# NS_Integrator.net
KiCad netlist of a schematic drawn in EAGLE
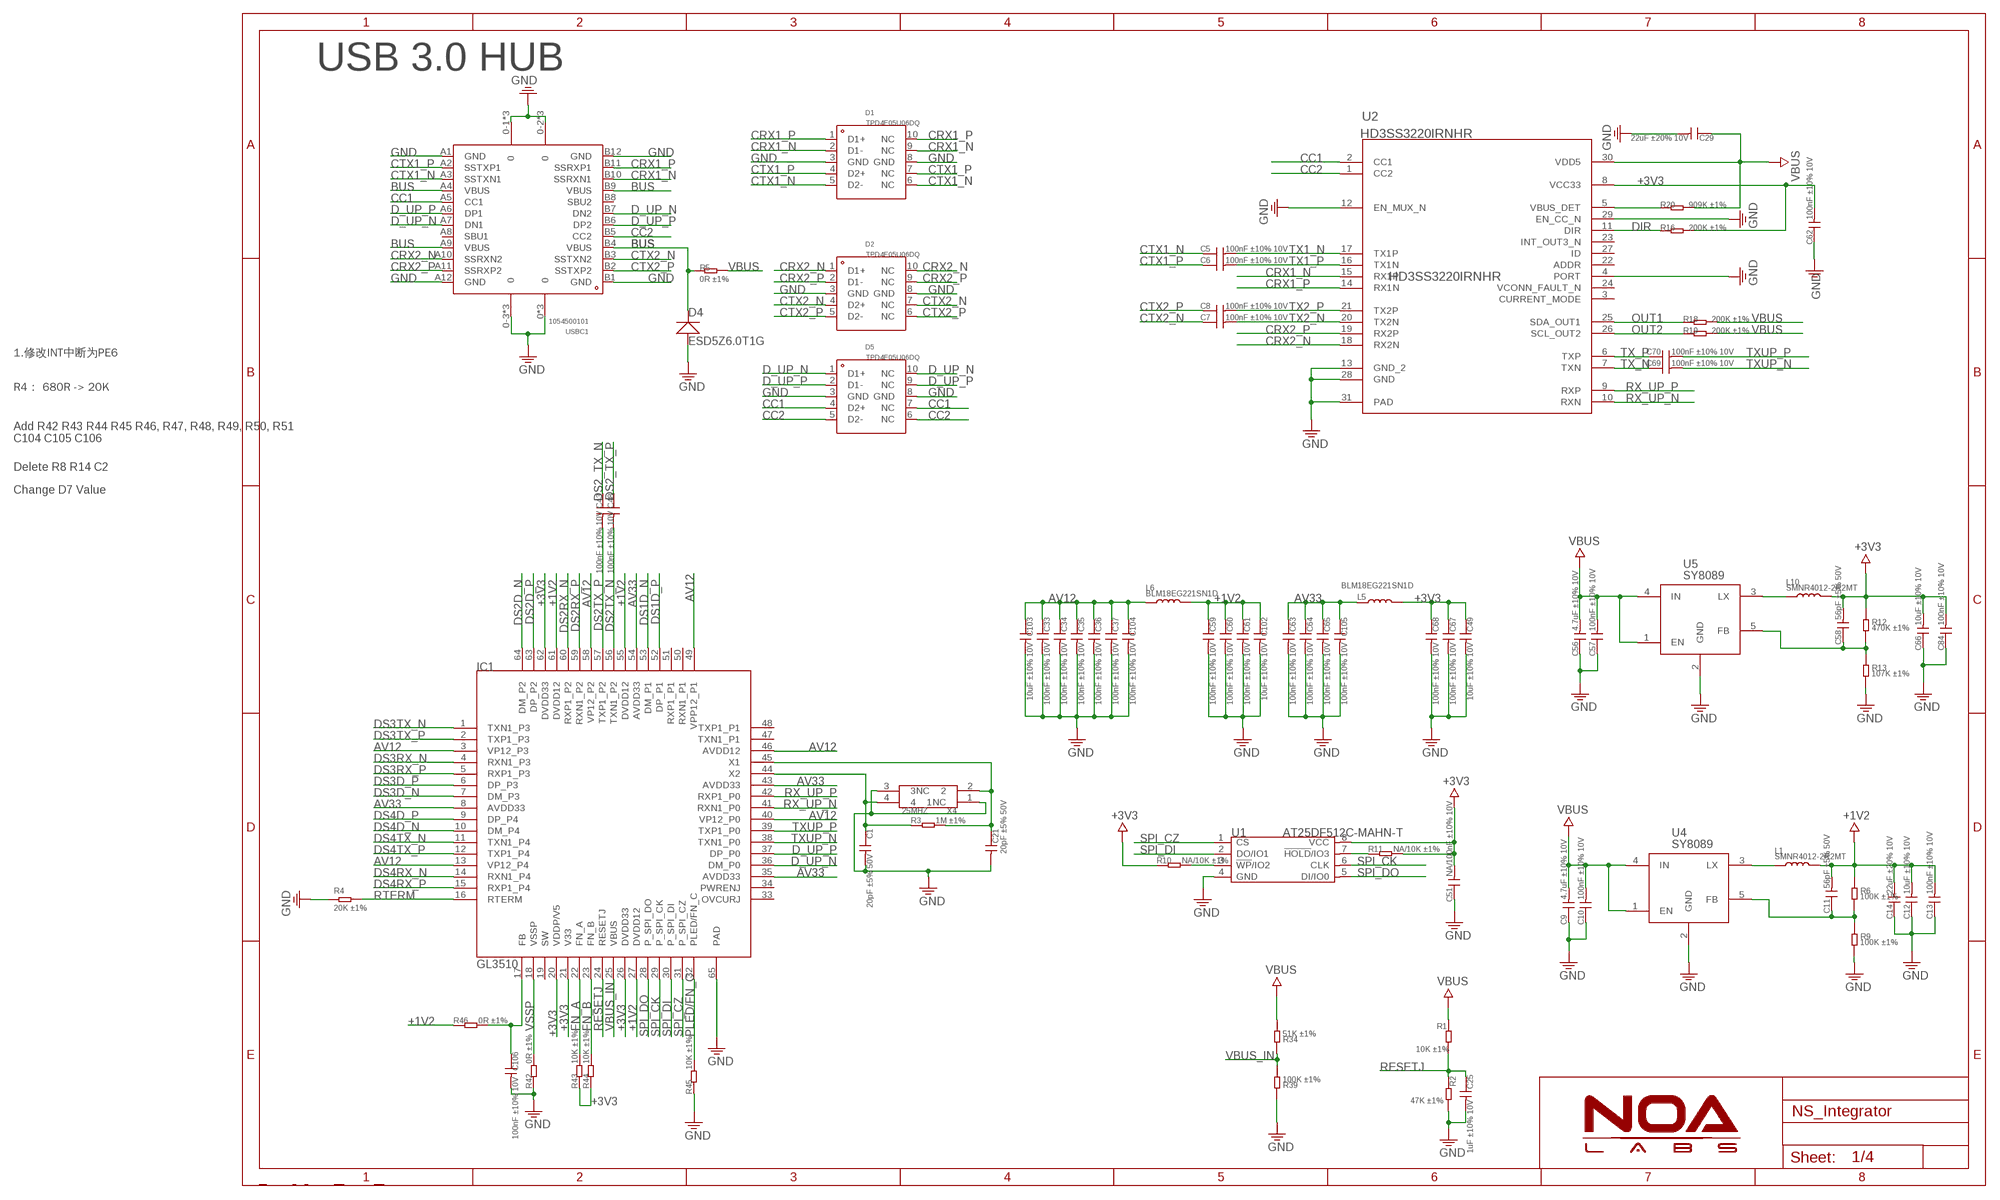
[diagram p0: schematic, sheet 1]
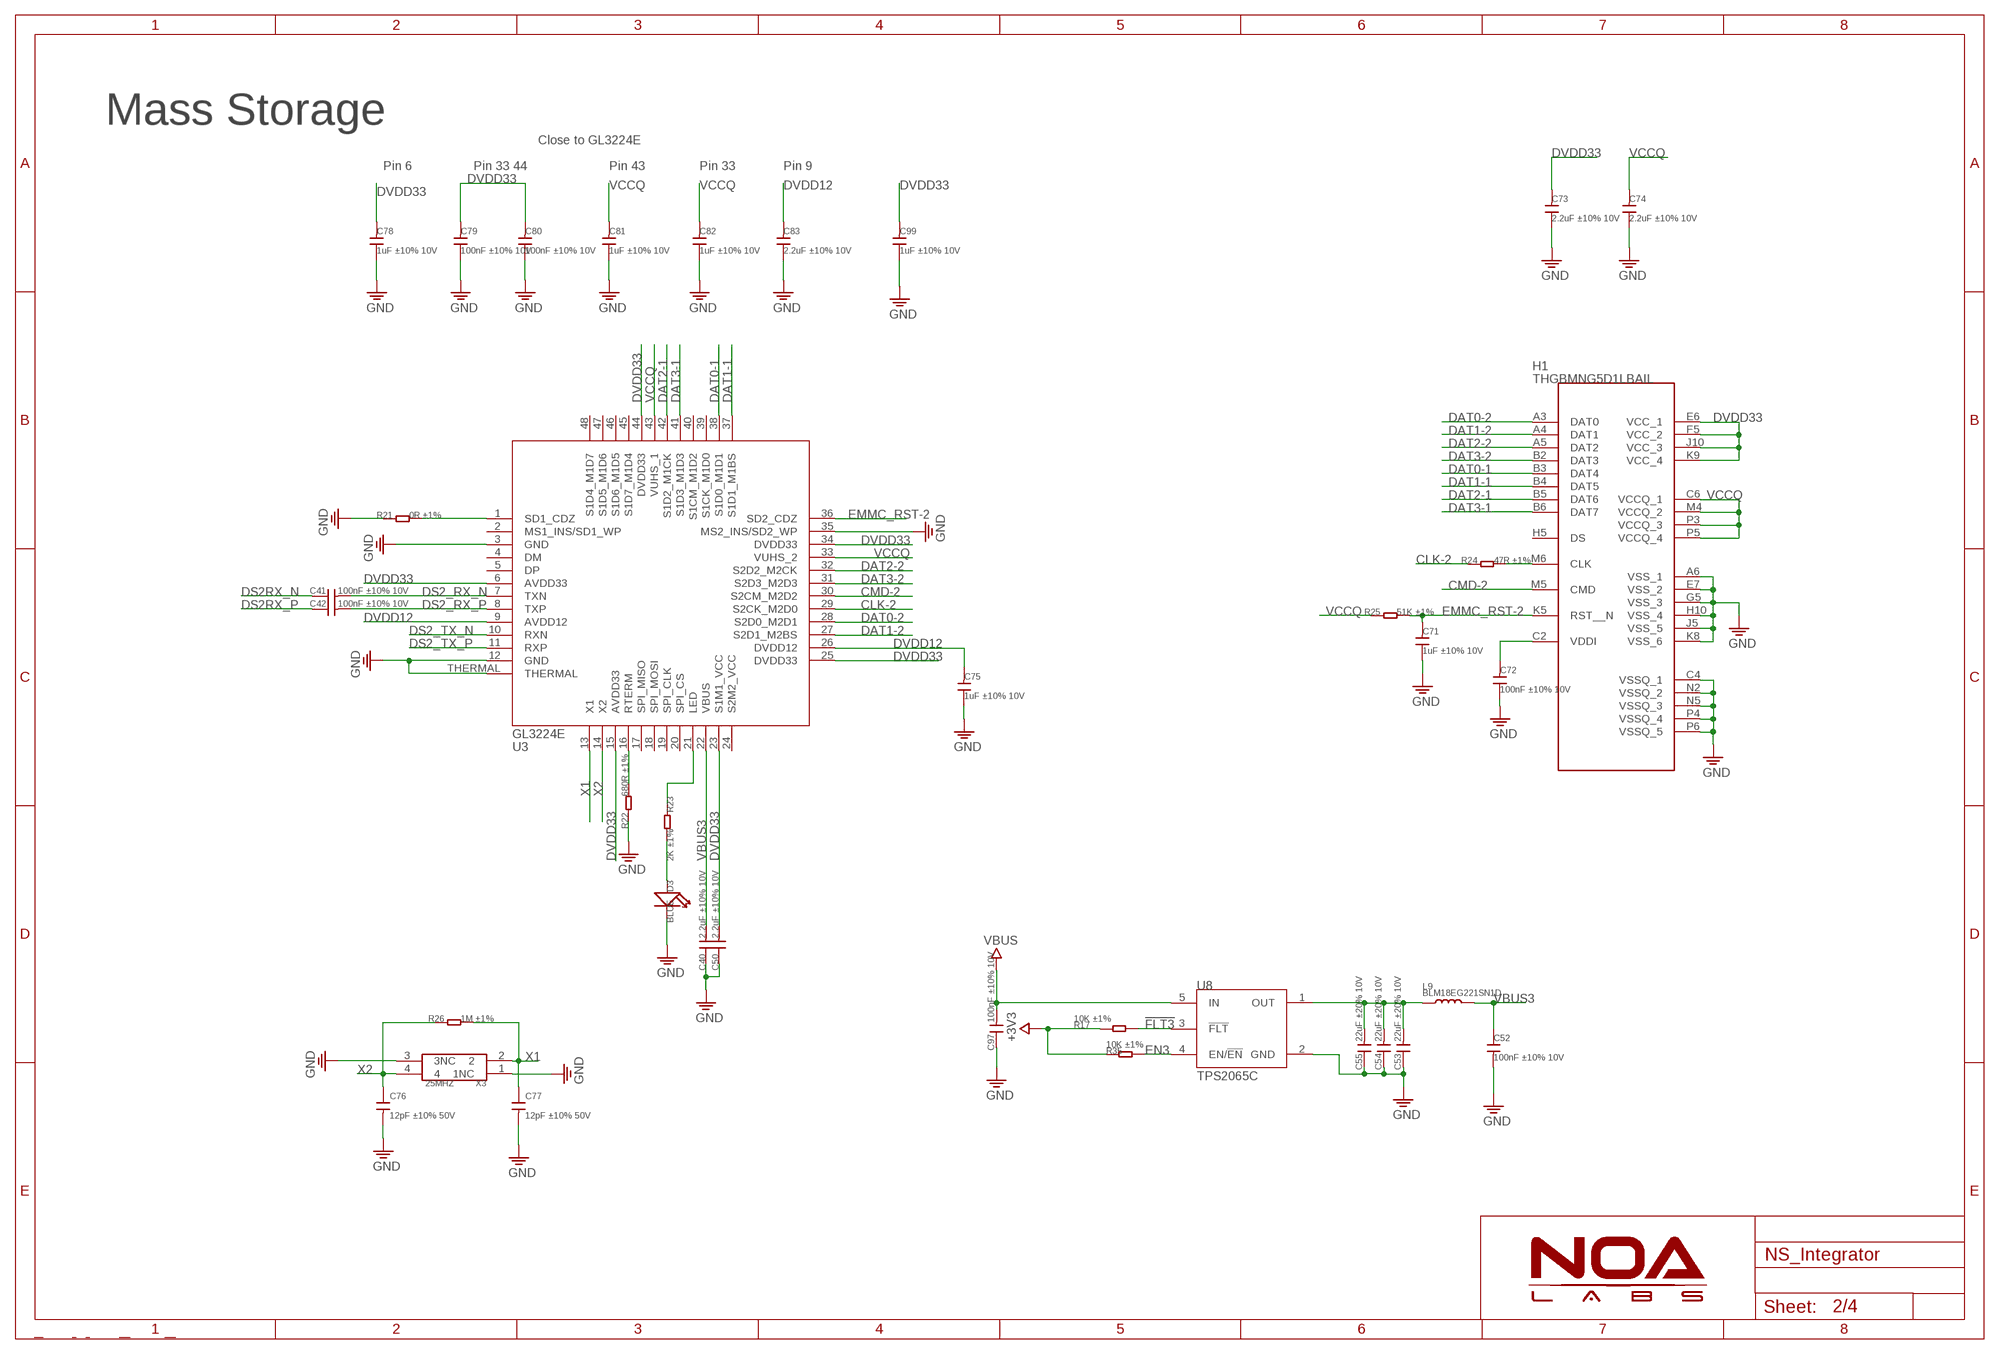
[diagram p1: schematic, sheet 2]
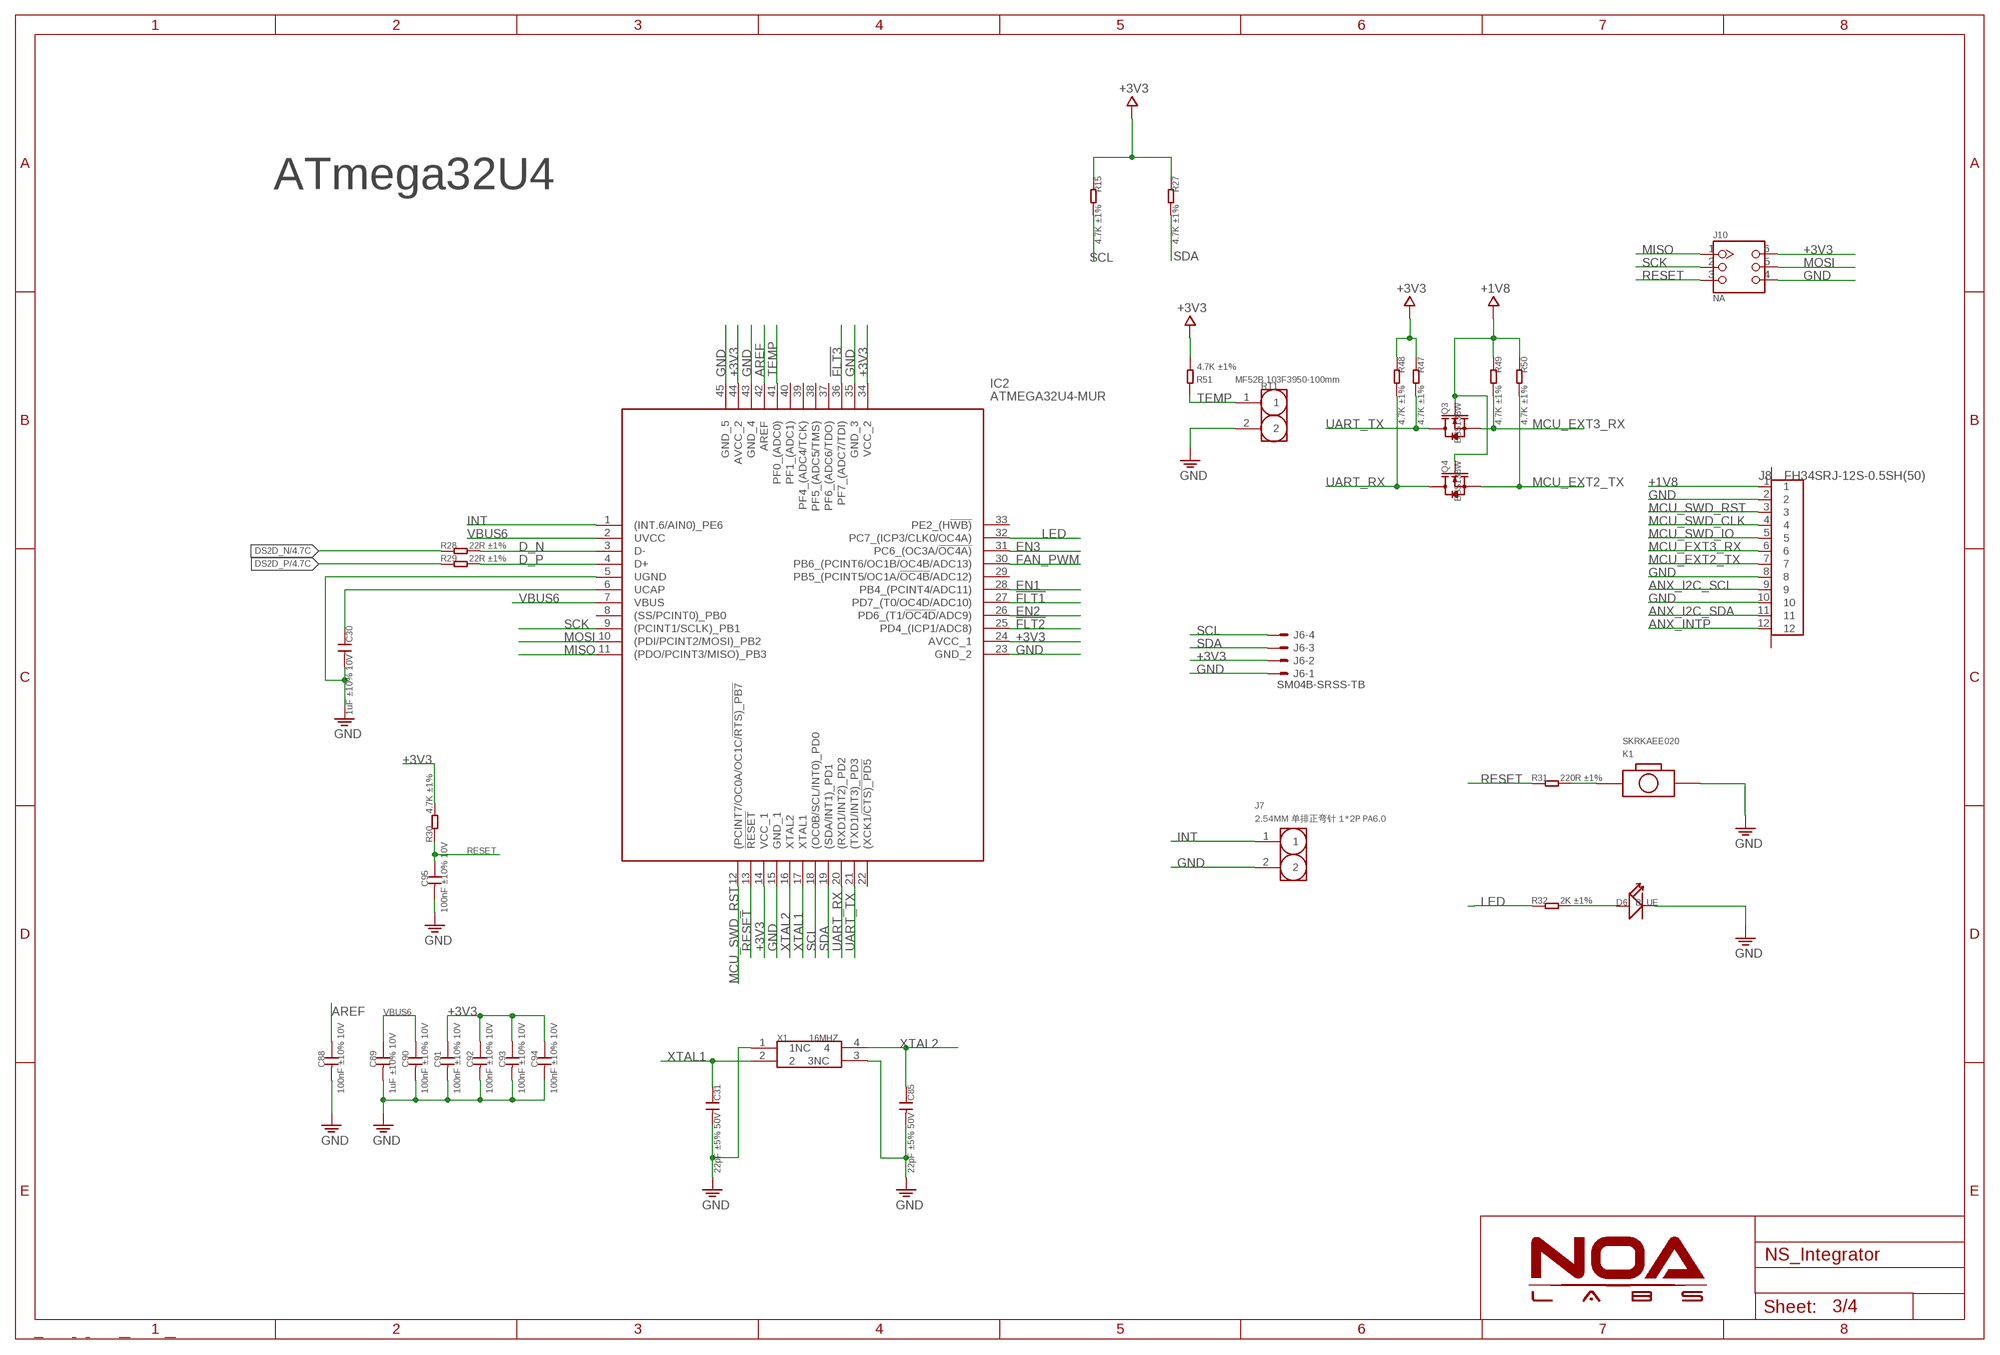
[diagram p2: schematic, sheet 3]
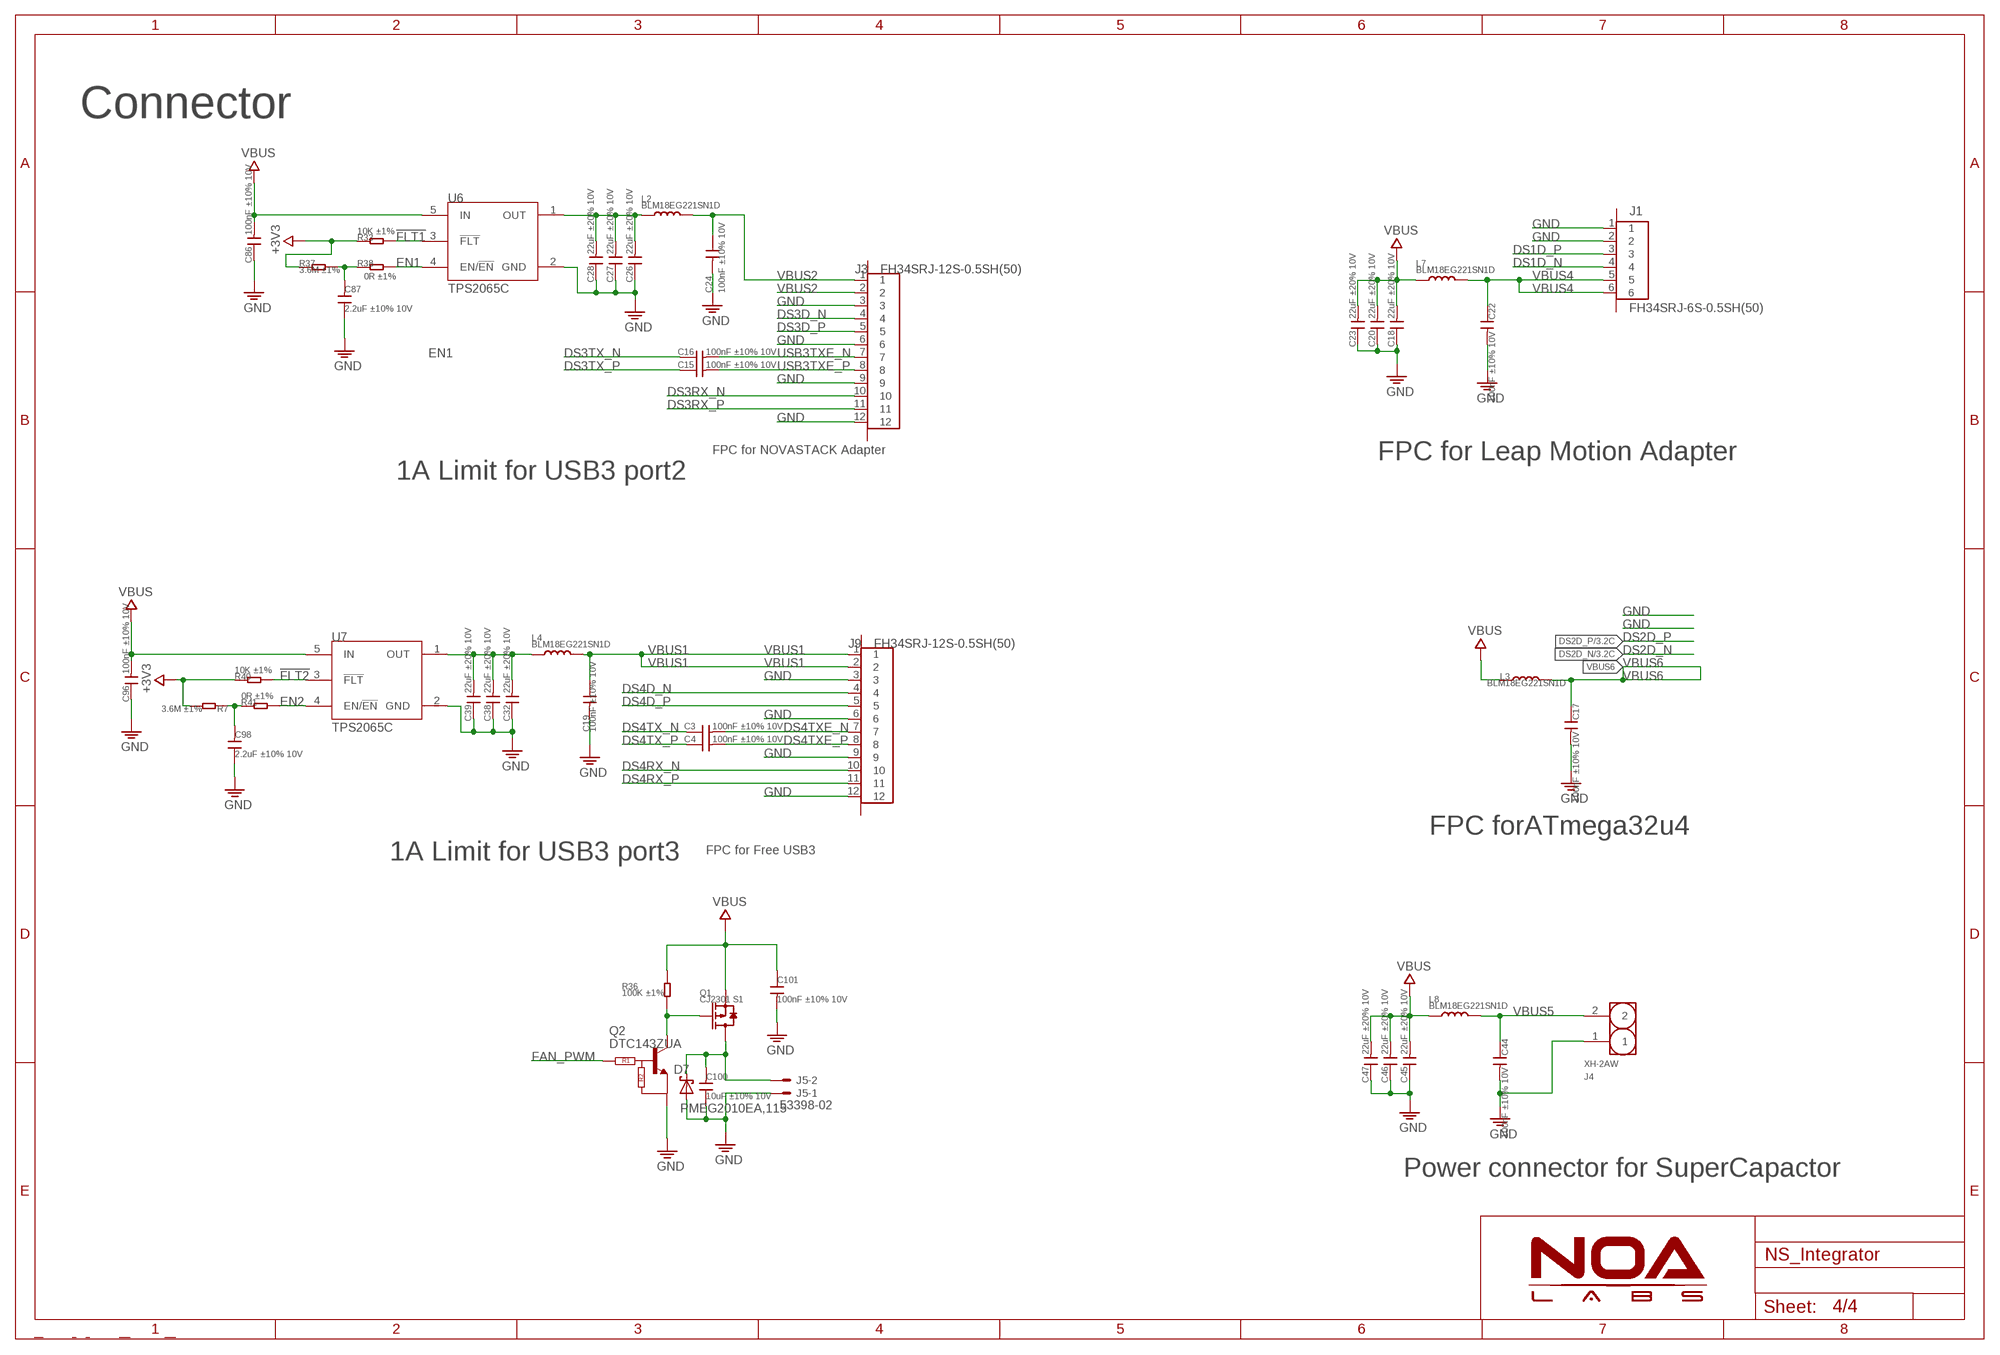
[diagram p3: schematic, sheet 4]

(export (version "E")
  (design (tool "Eeschema 10.0.6"))
  (components
    (comp (ref "C40")
      (value "2.2uF ±10% 10V")
      (footprint "eagle-import:C0402")
      (libsource (lib "eagle-import") (part "C-0402"))
    )
    (comp (ref "C41")
      (value "100nF ±10% 10V")
      (footprint "eagle-import:C0201")
      (libsource (lib "eagle-import") (part "C-0201"))
    )
    (comp (ref "C42")
      (value "100nF ±10% 10V")
      (footprint "eagle-import:C0201")
      (libsource (lib "eagle-import") (part "C-0201"))
    )
    (comp (ref "C50")
      (value "2.2uF ±10% 10V")
      (footprint "eagle-import:C0402")
      (libsource (lib "eagle-import") (part "C-0402"))
    )
    (comp (ref "C52")
      (value "100nF ±10% 10V")
      (footprint "eagle-import:C0402")
      (libsource (lib "eagle-import") (part "C-0402"))
    )
    (comp (ref "C53")
      (value "22uF ±20% 10V")
      (footprint "eagle-import:C0603")
      (libsource (lib "eagle-import") (part "C-0603"))
    )
    (comp (ref "C54")
      (value "22uF ±20% 10V")
      (footprint "eagle-import:C0603")
      (libsource (lib "eagle-import") (part "C-0603"))
    )
    (comp (ref "C55")
      (value "22uF ±20% 10V")
      (footprint "eagle-import:C0603")
      (libsource (lib "eagle-import") (part "C-0603"))
    )
    (comp (ref "C71")
      (value "1uF ±10% 10V")
      (footprint "eagle-import:C0402")
      (libsource (lib "eagle-import") (part "C-0402"))
    )
    (comp (ref "C72")
      (value "100nF ±10% 10V")
      (footprint "eagle-import:C0402")
      (libsource (lib "eagle-import") (part "C-0402"))
    )
    (comp (ref "C73")
      (value "2.2uF ±10% 10V")
      (footprint "eagle-import:C0402")
      (libsource (lib "eagle-import") (part "C-0402"))
    )
    (comp (ref "C74")
      (value "2.2uF ±10% 10V")
      (footprint "eagle-import:C0402")
      (libsource (lib "eagle-import") (part "C-0402"))
    )
    (comp (ref "C75")
      (value "1uF ±10% 10V")
      (footprint "eagle-import:C0402")
      (libsource (lib "eagle-import") (part "C-0402"))
    )
    (comp (ref "C76")
      (value "12pF ±10% 50V")
      (footprint "eagle-import:C0402")
      (libsource (lib "eagle-import") (part "C-0402"))
    )
    (comp (ref "C77")
      (value "12pF ±10% 50V")
      (footprint "eagle-import:C0402")
      (libsource (lib "eagle-import") (part "C-0402"))
    )
    (comp (ref "C78")
      (value "1uF ±10% 10V")
      (footprint "eagle-import:C0402")
      (libsource (lib "eagle-import") (part "C-0402"))
    )
    (comp (ref "C79")
      (value "100nF ±10% 10V")
      (footprint "eagle-import:C0402")
      (libsource (lib "eagle-import") (part "C-0402"))
    )
    (comp (ref "C80")
      (value "100nF ±10% 10V")
      (footprint "eagle-import:C0402")
      (libsource (lib "eagle-import") (part "C-0402"))
    )
    (comp (ref "C81")
      (value "1uF ±10% 10V")
      (footprint "eagle-import:C0402")
      (libsource (lib "eagle-import") (part "C-0402"))
    )
    (comp (ref "C82")
      (value "1uF ±10% 10V")
      (footprint "eagle-import:C0402")
      (libsource (lib "eagle-import") (part "C-0402"))
    )
    (comp (ref "C83")
      (value "2.2uF ±10% 10V")
      (footprint "eagle-import:C0402")
      (libsource (lib "eagle-import") (part "C-0402"))
    )
    (comp (ref "C97")
      (value "100nF ±10% 10V")
      (footprint "eagle-import:C0402")
      (libsource (lib "eagle-import") (part "C-0402"))
    )
    (comp (ref "C99")
      (value "1uF ±10% 10V")
      (footprint "eagle-import:C0402")
      (libsource (lib "eagle-import") (part "C-0402"))
    )
    (comp (ref "D3")
      (value "BLUE")
      (footprint "eagle-import:0402_LED")
      (libsource (lib "eagle-import") (part "LED-0402LED"))
    )
    (comp (ref "H1")
      (value "THGBMNG5D1LBAIL")
      (footprint "eagle-import:BGA153C50P14X14_11.5X13")
      (fields
        (field (name "MANUFACTURER_PART_NUMBER") "IS21ES04G-JCLI-TR")
        (field (name "MOUSER_PART_NUMBER") "870-IS21ES04GJCLITR")
      )
      (libsource (lib "eagle-import") (part "EMMC-SPECIALPAD"))
    )
    (comp (ref "L9")
      (value "BLM18EG221SN1D")
      (footprint "eagle-import:L0603")
      (libsource (lib "eagle-import") (part "L-0603"))
    )
    (comp (ref "R17")
      (value "10K ±1%")
      (footprint "eagle-import:R0402")
      (libsource (lib "eagle-import") (part "R-0402"))
    )
    (comp (ref "R21")
      (value "0R ±1%")
      (footprint "eagle-import:R0402")
      (libsource (lib "eagle-import") (part "R-0402"))
    )
    (comp (ref "R22")
      (value "680R ±1%")
      (footprint "eagle-import:R0402")
      (libsource (lib "eagle-import") (part "R-0402"))
    )
    (comp (ref "R23")
      (value "2K ±1%")
      (footprint "eagle-import:R0402")
      (libsource (lib "eagle-import") (part "R-0402"))
    )
    (comp (ref "R24")
      (value "47R ±1%")
      (footprint "eagle-import:R0402")
      (libsource (lib "eagle-import") (part "R-0402"))
    )
    (comp (ref "R25")
      (value "51K ±1%")
      (footprint "eagle-import:R0402")
      (libsource (lib "eagle-import") (part "R-0402"))
    )
    (comp (ref "R26")
      (value "1M ±1%")
      (footprint "eagle-import:R0402")
      (libsource (lib "eagle-import") (part "R-0402"))
    )
    (comp (ref "R35")
      (value "10K ±1%")
      (footprint "eagle-import:R0402")
      (libsource (lib "eagle-import") (part "R-0402"))
    )
    (comp (ref "U3")
      (value "GL3224E")
      (footprint "eagle-import:TQFN48_7MM")
      (libsource (lib "eagle-import") (part "GL3224E"))
    )
    (comp (ref "U8")
      (value "TPS2065C")
      (footprint "eagle-import:SOT23-5")
      (libsource (lib "eagle-import") (part "TPS20XXC"))
    )
    (comp (ref "X3")
      (value "25MHZ")
      (footprint "eagle-import:4P-SMD-2X1.6MM")
      (libsource (lib "eagle-import") (part "CRYSTAL-XTAL-4P"))
    )
    (comp (ref "C1")
      (value "20pF ±5% 50V")
      (footprint "eagle-import:C0402")
      (libsource (lib "eagle-import") (part "C-0402"))
    )
    (comp (ref "C5")
      (value "100nF ±10% 10V")
      (footprint "eagle-import:C0201")
      (libsource (lib "eagle-import") (part "C-0201"))
    )
    (comp (ref "C6")
      (value "100nF ±10% 10V")
      (footprint "eagle-import:C0201")
      (libsource (lib "eagle-import") (part "C-0201"))
    )
    (comp (ref "C7")
      (value "100nF ±10% 10V")
      (footprint "eagle-import:C0201")
      (libsource (lib "eagle-import") (part "C-0201"))
    )
    (comp (ref "C8")
      (value "100nF ±10% 10V")
      (footprint "eagle-import:C0201")
      (libsource (lib "eagle-import") (part "C-0201"))
    )
    (comp (ref "C9")
      (value "4.7uF ±10% 10V")
      (footprint "eagle-import:C0603")
      (libsource (lib "eagle-import") (part "C-0603"))
    )
    (comp (ref "C10")
      (value "100nF ±10% 10V")
      (footprint "eagle-import:C0402")
      (libsource (lib "eagle-import") (part "C-0402"))
    )
    (comp (ref "C11")
      (value "56pF ±5% 50V")
      (footprint "eagle-import:C0402")
      (libsource (lib "eagle-import") (part "C-0402"))
    )
    (comp (ref "C12")
      (value "10uF ±10% 10V")
      (footprint "eagle-import:C0603")
      (libsource (lib "eagle-import") (part "C-0603"))
    )
    (comp (ref "C13")
      (value "100nF ±10% 10V")
      (footprint "eagle-import:C0402")
      (libsource (lib "eagle-import") (part "C-0402"))
    )
    (comp (ref "C14")
      (value "22uF ±20% 10V")
      (footprint "eagle-import:C0805")
      (libsource (lib "eagle-import") (part "C-0805"))
    )
    (comp (ref "C21")
      (value "20pF ±5% 50V")
      (footprint "eagle-import:C0402")
      (libsource (lib "eagle-import") (part "C-0402"))
    )
    (comp (ref "C25")
      (value "1uF ±10% 10V")
      (footprint "eagle-import:C0402")
      (libsource (lib "eagle-import") (part "C-0402"))
    )
    (comp (ref "C29")
      (value "22uF ±20% 10V")
      (footprint "eagle-import:C0805")
      (libsource (lib "eagle-import") (part "C-0805"))
    )
    (comp (ref "C33")
      (value "100nF ±10% 10V")
      (footprint "eagle-import:C0402")
      (libsource (lib "eagle-import") (part "C-0402"))
    )
    (comp (ref "C34")
      (value "100nF ±10% 10V")
      (footprint "eagle-import:C0402")
      (libsource (lib "eagle-import") (part "C-0402"))
    )
    (comp (ref "C35")
      (value "100nF ±10% 10V")
      (footprint "eagle-import:C0402")
      (libsource (lib "eagle-import") (part "C-0402"))
    )
    (comp (ref "C36")
      (value "100nF ±10% 10V")
      (footprint "eagle-import:C0402")
      (libsource (lib "eagle-import") (part "C-0402"))
    )
    (comp (ref "C37")
      (value "100nF ±10% 10V")
      (footprint "eagle-import:C0402")
      (libsource (lib "eagle-import") (part "C-0402"))
    )
    (comp (ref "C43")
      (value "100nF ±10% 10V")
      (footprint "eagle-import:C0201")
      (libsource (lib "eagle-import") (part "C-0201"))
    )
    (comp (ref "C48")
      (value "100nF ±10% 10V")
      (footprint "eagle-import:C0201")
      (libsource (lib "eagle-import") (part "C-0201"))
    )
    (comp (ref "C49")
      (value "10uF ±10% 10V")
      (footprint "eagle-import:C0603")
      (libsource (lib "eagle-import") (part "C-0603"))
    )
    (comp (ref "C51")
      (value "NA/100nF ±10% 10V")
      (footprint "eagle-import:C0402")
      (libsource (lib "eagle-import") (part "C-0402"))
    )
    (comp (ref "C56")
      (value "4.7uF ±10% 10V")
      (footprint "eagle-import:C0603")
      (libsource (lib "eagle-import") (part "C-0603"))
    )
    (comp (ref "C57")
      (value "100nF ±10% 10V")
      (footprint "eagle-import:C0402")
      (libsource (lib "eagle-import") (part "C-0402"))
    )
    (comp (ref "C58")
      (value "56pF ±5% 50V")
      (footprint "eagle-import:C0402")
      (libsource (lib "eagle-import") (part "C-0402"))
    )
    (comp (ref "C59")
      (value "100nF ±10% 10V")
      (footprint "eagle-import:C0402")
      (libsource (lib "eagle-import") (part "C-0402"))
    )
    (comp (ref "C60")
      (value "100nF ±10% 10V")
      (footprint "eagle-import:C0402")
      (libsource (lib "eagle-import") (part "C-0402"))
    )
    (comp (ref "C61")
      (value "100nF ±10% 10V")
      (footprint "eagle-import:C0402")
      (libsource (lib "eagle-import") (part "C-0402"))
    )
    (comp (ref "C62")
      (value "100nF ±10% 10V")
      (footprint "eagle-import:C0402")
      (libsource (lib "eagle-import") (part "C-0402"))
    )
    (comp (ref "C63")
      (value "100nF ±10% 10V")
      (footprint "eagle-import:C0402")
      (libsource (lib "eagle-import") (part "C-0402"))
    )
    (comp (ref "C64")
      (value "100nF ±10% 10V")
      (footprint "eagle-import:C0402")
      (libsource (lib "eagle-import") (part "C-0402"))
    )
    (comp (ref "C65")
      (value "100nF ±10% 10V")
      (footprint "eagle-import:C0402")
      (libsource (lib "eagle-import") (part "C-0402"))
    )
    (comp (ref "C66")
      (value "10uF ±10% 10V")
      (footprint "eagle-import:C0603")
      (libsource (lib "eagle-import") (part "C-0603"))
    )
    (comp (ref "C67")
      (value "100nF ±10% 10V")
      (footprint "eagle-import:C0402")
      (libsource (lib "eagle-import") (part "C-0402"))
    )
    (comp (ref "C68")
      (value "100nF ±10% 10V")
      (footprint "eagle-import:C0402")
      (libsource (lib "eagle-import") (part "C-0402"))
    )
    (comp (ref "C69")
      (value "100nF ±10% 10V")
      (footprint "eagle-import:C0201")
      (libsource (lib "eagle-import") (part "C-0201"))
    )
    (comp (ref "C70")
      (value "100nF ±10% 10V")
      (footprint "eagle-import:C0201")
      (libsource (lib "eagle-import") (part "C-0201"))
    )
    (comp (ref "C84")
      (value "100nF ±10% 10V")
      (footprint "eagle-import:C0402")
      (libsource (lib "eagle-import") (part "C-0402"))
    )
    (comp (ref "C102")
      (value "10uF ±10% 10V")
      (footprint "eagle-import:C0603")
      (libsource (lib "eagle-import") (part "C-0603"))
    )
    (comp (ref "C103")
      (value "10uF ±10% 10V")
      (footprint "eagle-import:C0603")
      (libsource (lib "eagle-import") (part "C-0603"))
    )
    (comp (ref "C104")
      (value "100nF ±10% 10V")
      (footprint "eagle-import:C0402")
      (libsource (lib "eagle-import") (part "C-0402"))
    )
    (comp (ref "C105")
      (value "100nF ±10% 10V")
      (footprint "eagle-import:C0402")
      (libsource (lib "eagle-import") (part "C-0402"))
    )
    (comp (ref "C106")
      (value "100nF ±10% 10V")
      (footprint "eagle-import:C0402")
      (libsource (lib "eagle-import") (part "C-0402"))
    )
    (comp (ref "D1")
      (value "TPD4E05U06DQ")
      (footprint "eagle-import:USON-10_L2.5-W1.0-P0.50-BL")
      (fields
        (field (name "BOM_MANUFACTURER_PART") "TPD4E05U06DQAR")
        (field (name "BOM_SUPPLIER_PART") "C138714")
        (field (name "CONTRIBUTOR") "LCSC")
      )
      (libsource (lib "eagle-import") (part "TPD4E05U06DQARTPD4E05U06DQAR_C138714_USON-10_L2.5-W1.0-P0.50-BL"))
    )
    (comp (ref "D2")
      (value "TPD4E05U06DQ")
      (footprint "eagle-import:USON-10_L2.5-W1.0-P0.50-BL")
      (fields
        (field (name "BOM_MANUFACTURER_PART") "TPD4E05U06DQAR")
        (field (name "BOM_SUPPLIER_PART") "C138714")
        (field (name "CONTRIBUTOR") "LCSC")
      )
      (libsource (lib "eagle-import") (part "TPD4E05U06DQARTPD4E05U06DQAR_C138714_USON-10_L2.5-W1.0-P0.50-BL"))
    )
    (comp (ref "D4")
      (value "ESD5Z6.0T1G")
      (footprint "eagle-import:SOD523")
      (libsource (lib "eagle-import") (part "D-0603"))
    )
    (comp (ref "D5")
      (value "TPD4E05U06DQ")
      (footprint "eagle-import:USON-10_L2.5-W1.0-P0.50-BL")
      (fields
        (field (name "BOM_MANUFACTURER_PART") "TPD4E05U06DQAR")
        (field (name "BOM_SUPPLIER_PART") "C138714")
        (field (name "CONTRIBUTOR") "LCSC")
      )
      (libsource (lib "eagle-import") (part "TPD4E05U06DQARTPD4E05U06DQAR_C138714_USON-10_L2.5-W1.0-P0.50-BL"))
    )
    (comp (ref "IC1")
      (value "GL3510")
      (footprint "eagle-import:QFN40P800X800X80-65N")
      (libsource (lib "eagle-import") (part "GL3510"))
    )
    (comp (ref "L1")
      (value "SMNR4012-2R2MT")
      (footprint "eagle-import:L4012")
      (libsource (lib "eagle-import") (part "L-4012"))
    )
    (comp (ref "L5")
      (value "BLM18EG221SN1D")
      (footprint "eagle-import:L0603")
      (libsource (lib "eagle-import") (part "L-0603"))
    )
    (comp (ref "L6")
      (value "BLM18EG221SN1D")
      (footprint "eagle-import:L0603")
      (libsource (lib "eagle-import") (part "L-0603"))
    )
    (comp (ref "L10")
      (value "SMNR4012-2R2MT")
      (footprint "eagle-import:L4012")
      (libsource (lib "eagle-import") (part "L-4012"))
    )
    (comp (ref "R1")
      (value "10K ±1%")
      (footprint "eagle-import:R0402")
      (libsource (lib "eagle-import") (part "R-0402"))
    )
    (comp (ref "R2")
      (value "47K ±1%")
      (footprint "eagle-import:R0402")
      (libsource (lib "eagle-import") (part "R-0402"))
    )
    (comp (ref "R3")
      (value "1M ±1%")
      (footprint "eagle-import:R0402")
      (libsource (lib "eagle-import") (part "R-0402"))
    )
    (comp (ref "R4")
      (value "20K ±1%")
      (footprint "eagle-import:R0402")
      (libsource (lib "eagle-import") (part "R-0402"))
    )
    (comp (ref "R5")
      (value "0R ±1%")
      (footprint "eagle-import:R0805")
      (libsource (lib "eagle-import") (part "R-0805"))
    )
    (comp (ref "R6")
      (value "100K ±1%")
      (footprint "eagle-import:R0402")
      (libsource (lib "eagle-import") (part "R-0402"))
    )
    (comp (ref "R9")
      (value "100K ±1%")
      (footprint "eagle-import:R0402")
      (libsource (lib "eagle-import") (part "R-0402"))
    )
    (comp (ref "R10")
      (value "NA/10K ±1%")
      (footprint "eagle-import:R0402")
      (libsource (lib "eagle-import") (part "R-0402"))
    )
    (comp (ref "R11")
      (value "NA/10K ±1%")
      (footprint "eagle-import:R0402")
      (libsource (lib "eagle-import") (part "R-0402"))
    )
    (comp (ref "R12")
      (value "470K ±1%")
      (footprint "eagle-import:R0402")
      (libsource (lib "eagle-import") (part "R-0402"))
    )
    (comp (ref "R13")
      (value "107K ±1%")
      (footprint "eagle-import:R0402")
      (libsource (lib "eagle-import") (part "R-0402"))
    )
    (comp (ref "R16")
      (value "200K ±1%")
      (footprint "eagle-import:R0402")
      (libsource (lib "eagle-import") (part "R-0402"))
    )
    (comp (ref "R18")
      (value "200K ±1%")
      (footprint "eagle-import:R0402")
      (libsource (lib "eagle-import") (part "R-0402"))
    )
    (comp (ref "R19")
      (value "200K ±1%")
      (footprint "eagle-import:R0402")
      (libsource (lib "eagle-import") (part "R-0402"))
    )
    (comp (ref "R20")
      (value "909K ±1%")
      (footprint "eagle-import:R0402")
      (libsource (lib "eagle-import") (part "R-0402"))
    )
    (comp (ref "R34")
      (value "51K ±1%")
      (footprint "eagle-import:R0402")
      (libsource (lib "eagle-import") (part "R-0402"))
    )
    (comp (ref "R39")
      (value "100K ±1%")
      (footprint "eagle-import:R0402")
      (libsource (lib "eagle-import") (part "R-0402"))
    )
    (comp (ref "R42")
      (value "0R ±1%")
      (footprint "eagle-import:R0402")
      (libsource (lib "eagle-import") (part "R-0402"))
    )
    (comp (ref "R43")
      (value "10K ±1%")
      (footprint "eagle-import:R0402")
      (libsource (lib "eagle-import") (part "R-0402"))
    )
    (comp (ref "R44")
      (value "10K ±1%")
      (footprint "eagle-import:R0402")
      (libsource (lib "eagle-import") (part "R-0402"))
    )
    (comp (ref "R45")
      (value "10K ±1%")
      (footprint "eagle-import:R0402")
      (libsource (lib "eagle-import") (part "R-0402"))
    )
    (comp (ref "R46")
      (value "0R ±1%")
      (footprint "eagle-import:R0402")
      (libsource (lib "eagle-import") (part "R-0402"))
    )
    (comp (ref "U1")
      (value "AT25DF512C-MAHN-T")
      (footprint "eagle-import:SOIC8-6.0")
      (libsource (lib "eagle-import") (part "W25Q"))
    )
    (comp (ref "U2")
      (value "HD3SS3220IRNHR")
      (footprint "eagle-import:RNH0030A")
      (fields (field (name "MANUFACTURER") "Texas Instruments"))
      (libsource (lib "eagle-import") (part "HD3SS3220IRNHR"))
    )
    (comp (ref "U4")
      (value "SY8089")
      (footprint "eagle-import:SOT23-5")
      (libsource (lib "eagle-import") (part "SY8089"))
    )
    (comp (ref "U5")
      (value "SY8089")
      (footprint "eagle-import:SOT23-5")
      (libsource (lib "eagle-import") (part "SY8089"))
    )
    (comp (ref "USBC1")
      (value "1054500101")
      (footprint "eagle-import:USB-C-SMD_TYPE-C-USB-18")
      (fields
        (field (name "BOM_MANUFACTURER_PART") "105450-0101")
        (field (name "BOM_SUPPLIER_PART") "C134092")
        (field (name "CONTRIBUTOR") "LCSC")
      )
      (libsource (lib "eagle-import") (part "TYPEC-105450-0101105450-0101_USB-C-SMD_TYPE-C-USB-18"))
    )
    (comp (ref "X4")
      (value "25MHZ")
      (footprint "eagle-import:4P-SMD-2X1.6MM")
      (libsource (lib "eagle-import") (part "CRYSTAL-XTAL-4P"))
    )
    (comp (ref "C3")
      (value "100nF ±10% 10V")
      (footprint "eagle-import:C0201")
      (libsource (lib "eagle-import") (part "C-0201"))
    )
    (comp (ref "C4")
      (value "100nF ±10% 10V")
      (footprint "eagle-import:C0201")
      (libsource (lib "eagle-import") (part "C-0201"))
    )
    (comp (ref "C15")
      (value "100nF ±10% 10V")
      (footprint "eagle-import:C0201")
      (libsource (lib "eagle-import") (part "C-0201"))
    )
    (comp (ref "C16")
      (value "100nF ±10% 10V")
      (footprint "eagle-import:C0201")
      (libsource (lib "eagle-import") (part "C-0201"))
    )
    (comp (ref "C17")
      (value "100nF ±10% 10V")
      (footprint "eagle-import:C0402")
      (libsource (lib "eagle-import") (part "C-0402"))
    )
    (comp (ref "C18")
      (value "22uF ±20% 10V")
      (footprint "eagle-import:C0603")
      (libsource (lib "eagle-import") (part "C-0603"))
    )
    (comp (ref "C19")
      (value "100nF ±10% 10V")
      (footprint "eagle-import:C0402")
      (libsource (lib "eagle-import") (part "C-0402"))
    )
    (comp (ref "C20")
      (value "22uF ±20% 10V")
      (footprint "eagle-import:C0603")
      (libsource (lib "eagle-import") (part "C-0603"))
    )
    (comp (ref "C22")
      (value "100nF ±10% 10V")
      (footprint "eagle-import:C0402")
      (libsource (lib "eagle-import") (part "C-0402"))
    )
    (comp (ref "C23")
      (value "22uF ±20% 10V")
      (footprint "eagle-import:C0603")
      (libsource (lib "eagle-import") (part "C-0603"))
    )
    (comp (ref "C24")
      (value "100nF ±10% 10V")
      (footprint "eagle-import:C0402")
      (libsource (lib "eagle-import") (part "C-0402"))
    )
    (comp (ref "C26")
      (value "22uF ±20% 10V")
      (footprint "eagle-import:C0603")
      (libsource (lib "eagle-import") (part "C-0603"))
    )
    (comp (ref "C27")
      (value "22uF ±20% 10V")
      (footprint "eagle-import:C0603")
      (libsource (lib "eagle-import") (part "C-0603"))
    )
    (comp (ref "C28")
      (value "22uF ±20% 10V")
      (footprint "eagle-import:C0603")
      (libsource (lib "eagle-import") (part "C-0603"))
    )
    (comp (ref "C32")
      (value "22uF ±20% 10V")
      (footprint "eagle-import:C0603")
      (libsource (lib "eagle-import") (part "C-0603"))
    )
    (comp (ref "C38")
      (value "22uF ±20% 10V")
      (footprint "eagle-import:C0603")
      (libsource (lib "eagle-import") (part "C-0603"))
    )
    (comp (ref "C39")
      (value "22uF ±20% 10V")
      (footprint "eagle-import:C0603")
      (libsource (lib "eagle-import") (part "C-0603"))
    )
    (comp (ref "C44")
      (value "100nF ±10% 10V")
      (footprint "eagle-import:C0402")
      (libsource (lib "eagle-import") (part "C-0402"))
    )
    (comp (ref "C45")
      (value "22uF ±20% 10V")
      (footprint "eagle-import:C0603")
      (libsource (lib "eagle-import") (part "C-0603"))
    )
    (comp (ref "C46")
      (value "22uF ±20% 10V")
      (footprint "eagle-import:C0603")
      (libsource (lib "eagle-import") (part "C-0603"))
    )
    (comp (ref "C47")
      (value "22uF ±20% 10V")
      (footprint "eagle-import:C0603")
      (libsource (lib "eagle-import") (part "C-0603"))
    )
    (comp (ref "C86")
      (value "100nF ±10% 10V")
      (footprint "eagle-import:C0402")
      (libsource (lib "eagle-import") (part "C-0402"))
    )
    (comp (ref "C87")
      (value "2.2uF ±10% 10V")
      (footprint "eagle-import:C0402")
      (libsource (lib "eagle-import") (part "C-0402"))
    )
    (comp (ref "C96")
      (value "100nF ±10% 10V")
      (footprint "eagle-import:C0402")
      (libsource (lib "eagle-import") (part "C-0402"))
    )
    (comp (ref "C98")
      (value "2.2uF ±10% 10V")
      (footprint "eagle-import:C0402")
      (libsource (lib "eagle-import") (part "C-0402"))
    )
    (comp (ref "C100")
      (value "10uF ±10% 10V")
      (footprint "eagle-import:C0603")
      (libsource (lib "eagle-import") (part "C-0603"))
    )
    (comp (ref "C101")
      (value "100nF ±10% 10V")
      (footprint "eagle-import:C0402")
      (libsource (lib "eagle-import") (part "C-0402"))
    )
    (comp (ref "D7")
      (value "PMEG2010EA,115")
      (footprint "eagle-import:SOD323")
      (libsource (lib "eagle-import") (part "SCHOTTKY-SOD323"))
    )
    (comp (ref "J1")
      (value "FH34SRJ-6S-0.5SH(50)")
      (footprint "eagle-import:FH34RJ-6S")
      (libsource (lib "eagle-import") (part "FPC-0.5-6P-FH34RJ"))
    )
    (comp (ref "J3")
      (value "FH34SRJ-12S-0.5SH(50)")
      (footprint "eagle-import:FPC-0.5-12P")
      (libsource (lib "eagle-import") (part "FPC-0.5-12PFPC-0.5-12P"))
    )
    (comp (ref "J4")
      (value "XH-2AW")
      (footprint "eagle-import:XH-02-90")
      (libsource (lib "eagle-import") (part "HEADER-2P-90DEG-FEMALE"))
    )
    (comp (ref "J5")
      (value "53398-02")
      (footprint "eagle-import:53398-02")
      (fields (field (name "MF") "MOLEX"))
      (libsource (lib "eagle-import") (part "53?-02398"))
    )
    (comp (ref "J9")
      (value "FH34SRJ-12S-0.5SH(50)")
      (footprint "eagle-import:FPC-0.5-12P")
      (libsource (lib "eagle-import") (part "FPC-0.5-12PFPC-0.5-12P"))
    )
    (comp (ref "L2")
      (value "BLM18EG221SN1D")
      (footprint "eagle-import:L0603")
      (libsource (lib "eagle-import") (part "L-0603"))
    )
    (comp (ref "L3")
      (value "BLM18EG221SN1D")
      (footprint "eagle-import:L0603")
      (libsource (lib "eagle-import") (part "L-0603"))
    )
    (comp (ref "L4")
      (value "BLM18EG221SN1D")
      (footprint "eagle-import:L0603")
      (libsource (lib "eagle-import") (part "L-0603"))
    )
    (comp (ref "L7")
      (value "BLM18EG221SN1D")
      (footprint "eagle-import:L0603")
      (libsource (lib "eagle-import") (part "L-0603"))
    )
    (comp (ref "L8")
      (value "BLM18EG221SN1D")
      (footprint "eagle-import:L0603")
      (libsource (lib "eagle-import") (part "L-0603"))
    )
    (comp (ref "Q1")
      (value "CJ2301 S1")
      (footprint "eagle-import:SOT23")
      (libsource (lib "eagle-import") (part "MOSFET-P-SOT23"))
    )
    (comp (ref "Q2")
      (value "DTC143ZUA")
      (footprint "eagle-import:SOT323")
      (libsource (lib "eagle-import") (part "DIGITAL-NPNUE"))
    )
    (comp (ref "R7")
      (value "3.6M ±1%")
      (footprint "eagle-import:R0402")
      (libsource (lib "eagle-import") (part "R-0402"))
    )
    (comp (ref "R33")
      (value "10K ±1%")
      (footprint "eagle-import:R0402")
      (libsource (lib "eagle-import") (part "R-0402"))
    )
    (comp (ref "R36")
      (value "100K ±1%")
      (footprint "eagle-import:R0402")
      (libsource (lib "eagle-import") (part "R-0402"))
    )
    (comp (ref "R37")
      (value "3.6M ±1%")
      (footprint "eagle-import:R0402")
      (libsource (lib "eagle-import") (part "R-0402"))
    )
    (comp (ref "R38")
      (value "0R ±1%")
      (footprint "eagle-import:R0402")
      (libsource (lib "eagle-import") (part "R-0402"))
    )
    (comp (ref "R40")
      (value "10K ±1%")
      (footprint "eagle-import:R0402")
      (libsource (lib "eagle-import") (part "R-0402"))
    )
    (comp (ref "R41")
      (value "0R ±1%")
      (footprint "eagle-import:R0402")
      (libsource (lib "eagle-import") (part "R-0402"))
    )
    (comp (ref "U6")
      (value "TPS2065C")
      (footprint "eagle-import:SOT23-5")
      (libsource (lib "eagle-import") (part "TPS20XXC"))
    )
    (comp (ref "U7")
      (value "TPS2065C")
      (footprint "eagle-import:SOT23-5")
      (libsource (lib "eagle-import") (part "TPS20XXC"))
    )
    (comp (ref "C30")
      (value "1uF ±10% 10V")
      (footprint "eagle-import:C0402")
      (libsource (lib "eagle-import") (part "C-0402"))
    )
    (comp (ref "C31")
      (value "22pF ±5% 50V")
      (footprint "eagle-import:C0402")
      (libsource (lib "eagle-import") (part "C-0402"))
    )
    (comp (ref "C85")
      (value "22pF ±5% 50V")
      (footprint "eagle-import:C0402")
      (libsource (lib "eagle-import") (part "C-0402"))
    )
    (comp (ref "C88")
      (value "100nF ±10% 10V")
      (footprint "eagle-import:C0402")
      (libsource (lib "eagle-import") (part "C-0402"))
    )
    (comp (ref "C89")
      (value "1uF ±10% 10V")
      (footprint "eagle-import:C0402")
      (libsource (lib "eagle-import") (part "C-0402"))
    )
    (comp (ref "C90")
      (value "100nF ±10% 10V")
      (footprint "eagle-import:C0402")
      (libsource (lib "eagle-import") (part "C-0402"))
    )
    (comp (ref "C91")
      (value "100nF ±10% 10V")
      (footprint "eagle-import:C0402")
      (libsource (lib "eagle-import") (part "C-0402"))
    )
    (comp (ref "C92")
      (value "100nF ±10% 10V")
      (footprint "eagle-import:C0402")
      (libsource (lib "eagle-import") (part "C-0402"))
    )
    (comp (ref "C93")
      (value "100nF ±10% 10V")
      (footprint "eagle-import:C0402")
      (libsource (lib "eagle-import") (part "C-0402"))
    )
    (comp (ref "C94")
      (value "100nF ±10% 10V")
      (footprint "eagle-import:C0402")
      (libsource (lib "eagle-import") (part "C-0402"))
    )
    (comp (ref "C95")
      (value "100nF ±10% 10V")
      (footprint "eagle-import:C0402")
      (libsource (lib "eagle-import") (part "C-0402"))
    )
    (comp (ref "D6")
      (value "BLUE")
      (footprint "eagle-import:0402_LED")
      (libsource (lib "eagle-import") (part "LED-0402LED"))
    )
    (comp (ref "IC2")
      (value "ATMEGA32U4-MUR")
      (footprint "eagle-import:QFN50P700X700X100-45N")
      (fields
        (field (name "MANUFACTURER_PART_NUMBER") "ATMEGA32U4-MU")
        (field (name "MOUSER_PART_NUMBER") "556-ATMEGA32U4-MU")
        (field (name "RS_PART_NUMBER") "1310290P")
      )
      (libsource (lib "eagle-import") (part "ATMEGA32U4-MU"))
    )
    (comp (ref "J6")
      (value "SM04B-SRSS-TB")
      (footprint "eagle-import:SM04B-SRSS-TB")
      (libsource (lib "eagle-import") (part "?M04B-SRSS-TBS"))
    )
    (comp (ref "J7")
      (value "2.54MM 单排正弯针 1*2P PA6.0")
      (footprint "eagle-import:2P-2.54-65_35MIL")
      (libsource (lib "eagle-import") (part "HEADER-2P-65/35MIL"))
    )
    (comp (ref "J8")
      (value "FH34SRJ-12S-0.5SH(50)")
      (footprint "eagle-import:FPC-0.5-12P")
      (libsource (lib "eagle-import") (part "FPC-0.5-12PFPC-0.5-12P"))
    )
    (comp (ref "J10")
      (value "NA")
      (footprint "eagle-import:2X3P-2.54-65_35MIL")
      (libsource (lib "eagle-import") (part "HEADER-2X3P-THT"))
    )
    (comp (ref "K1")
      (value "SKRKAEE020")
      (footprint "eagle-import:SKRKAEE020")
      (libsource (lib "eagle-import") (part "BUTTON-2PSKRKAEE020"))
    )
    (comp (ref "Q3")
      (value "BSS138W")
      (footprint "eagle-import:SOT-323")
      (libsource (lib "eagle-import") (part "MOSFET-N-323"))
    )
    (comp (ref "Q4")
      (value "BSS138W")
      (footprint "eagle-import:SOT-323")
      (libsource (lib "eagle-import") (part "MOSFET-N-323"))
    )
    (comp (ref "R15")
      (value "4.7K ±1%")
      (footprint "eagle-import:R0402")
      (libsource (lib "eagle-import") (part "R-0402"))
    )
    (comp (ref "R27")
      (value "4.7K ±1%")
      (footprint "eagle-import:R0402")
      (libsource (lib "eagle-import") (part "R-0402"))
    )
    (comp (ref "R28")
      (value "22R ±1%")
      (footprint "eagle-import:R0402")
      (libsource (lib "eagle-import") (part "R-0402"))
    )
    (comp (ref "R29")
      (value "22R ±1%")
      (footprint "eagle-import:R0402")
      (libsource (lib "eagle-import") (part "R-0402"))
    )
    (comp (ref "R30")
      (value "4.7K ±1%")
      (footprint "eagle-import:R0402")
      (libsource (lib "eagle-import") (part "R-0402"))
    )
    (comp (ref "R31")
      (value "220R ±1%")
      (footprint "eagle-import:R0402")
      (libsource (lib "eagle-import") (part "R-0402"))
    )
    (comp (ref "R32")
      (value "2K ±1%")
      (footprint "eagle-import:R0402")
      (libsource (lib "eagle-import") (part "R-0402"))
    )
    (comp (ref "R47")
      (value "4.7K ±1%")
      (footprint "eagle-import:R0402")
      (libsource (lib "eagle-import") (part "R-0402"))
    )
    (comp (ref "R48")
      (value "4.7K ±1%")
      (footprint "eagle-import:R0402")
      (libsource (lib "eagle-import") (part "R-0402"))
    )
    (comp (ref "R49")
      (value "4.7K ±1%")
      (footprint "eagle-import:R0402")
      (libsource (lib "eagle-import") (part "R-0402"))
    )
    (comp (ref "R50")
      (value "4.7K ±1%")
      (footprint "eagle-import:R0402")
      (libsource (lib "eagle-import") (part "R-0402"))
    )
    (comp (ref "R51")
      (value "4.7K ±1%")
      (footprint "eagle-import:R0402")
      (libsource (lib "eagle-import") (part "R-0402"))
    )
    (comp (ref "RT1")
      (value "MF52B 103F3950-100mm")
      (footprint "eagle-import:2P-1.27")
      (libsource (lib "eagle-import") (part "HEADER-2P-1.27"))
    )
    (comp (ref "X1")
      (value "16MHZ")
      (footprint "eagle-import:4P-SMD-3.2X2.5")
      (libsource (lib "eagle-import") (part "CRYSTAL-XTAL-4P-3225"))
    )
  )
  (nets
    (net (code "1") (name "+1V2") (class "Default")
      (node (ref "C102") (pin "1") (pinfunction "1_1") (pintype "passive"))
      (node (ref "C11") (pin "2") (pinfunction "2_2") (pintype "passive"))
      (node (ref "C12") (pin "2") (pinfunction "2_2") (pintype "passive"))
      (node (ref "C13") (pin "2") (pinfunction "2_2") (pintype "passive"))
      (node (ref "C14") (pin "2") (pinfunction "2_2") (pintype "passive"))
      (node (ref "C59") (pin "1") (pinfunction "1_1") (pintype "passive"))
      (node (ref "C60") (pin "1") (pinfunction "1_1") (pintype "passive"))
      (node (ref "C61") (pin "1") (pinfunction "1_1") (pintype "passive"))
      (node (ref "IC1") (pin "27") (pinfunction "DVDD12_27") (pintype "bidirectional"))
      (node (ref "IC1") (pin "55") (pinfunction "DVDD12_55") (pintype "bidirectional"))
      (node (ref "IC1") (pin "61") (pinfunction "DVDD12_61") (pintype "bidirectional"))
      (node (ref "L1") (pin "2") (pinfunction "2_2") (pintype "passive"))
      (node (ref "L6") (pin "2") (pinfunction "2_2") (pintype "passive"))
      (node (ref "R46") (pin "1") (pinfunction "1_1") (pintype "passive"))
      (node (ref "R6") (pin "1") (pinfunction "1_1") (pintype "passive"))
    )
    (net (code "2") (name "+1V8") (class "Default")
      (node (ref "J8") (pin "1") (pinfunction "1_1") (pintype "bidirectional"))
      (node (ref "Q3") (pin "1") (pinfunction "G_1") (pintype "passive"))
      (node (ref "Q4") (pin "1") (pinfunction "G_1") (pintype "passive"))
      (node (ref "R49") (pin "1") (pinfunction "1_1") (pintype "passive"))
      (node (ref "R50") (pin "1") (pinfunction "1_1") (pintype "passive"))
    )
    (net (code "3") (name "+3V3") (class "Default")
      (node (ref "C49") (pin "1") (pinfunction "1_1") (pintype "passive"))
      (node (ref "C51") (pin "2") (pinfunction "2_2") (pintype "passive"))
      (node (ref "C58") (pin "2") (pinfunction "2_2") (pintype "passive"))
      (node (ref "C62") (pin "2") (pinfunction "2_2") (pintype "passive"))
      (node (ref "C66") (pin "2") (pinfunction "2_2") (pintype "passive"))
      (node (ref "C67") (pin "1") (pinfunction "1_1") (pintype "passive"))
      (node (ref "C68") (pin "1") (pinfunction "1_1") (pintype "passive"))
      (node (ref "C84") (pin "2") (pinfunction "2_2") (pintype "passive"))
      (node (ref "C91") (pin "1") (pinfunction "1_1") (pintype "passive"))
      (node (ref "C92") (pin "1") (pinfunction "1_1") (pintype "passive"))
      (node (ref "C93") (pin "1") (pinfunction "1_1") (pintype "passive"))
      (node (ref "C94") (pin "1") (pinfunction "1_1") (pintype "passive"))
      (node (ref "IC1") (pin "20") (pinfunction "VDDP/V5_20") (pintype "bidirectional"))
      (node (ref "IC1") (pin "21") (pinfunction "V33_21") (pintype "bidirectional"))
      (node (ref "IC1") (pin "26") (pinfunction "DVDD33_26") (pintype "bidirectional"))
      (node (ref "IC1") (pin "62") (pinfunction "DVDD33_62") (pintype "bidirectional"))
      (node (ref "IC2") (pin "14") (pinfunction "VCC_1_14") (pintype "bidirectional"))
      (node (ref "IC2") (pin "24") (pinfunction "AVCC_1_24") (pintype "bidirectional"))
      (node (ref "IC2") (pin "34") (pinfunction "VCC_2_34") (pintype "bidirectional"))
      (node (ref "IC2") (pin "44") (pinfunction "AVCC_2_44") (pintype "bidirectional"))
      (node (ref "J10") (pin "6") (pinfunction "6_6") (pintype "bidirectional"))
      (node (ref "J6") (pin "2") (pinfunction "S_2") (pintype "passive"))
      (node (ref "L10") (pin "2") (pinfunction "2_2") (pintype "passive"))
      (node (ref "L5") (pin "2") (pinfunction "2_2") (pintype "passive"))
      (node (ref "R10") (pin "1") (pinfunction "1_1") (pintype "passive"))
      (node (ref "R11") (pin "2") (pinfunction "2_2") (pintype "passive"))
      (node (ref "R12") (pin "1") (pinfunction "1_1") (pintype "passive"))
      (node (ref "R15") (pin "1") (pinfunction "1_1") (pintype "passive"))
      (node (ref "R16") (pin "2") (pinfunction "2_2") (pintype "passive"))
      (node (ref "R17") (pin "1") (pinfunction "1_1") (pintype "passive"))
      (node (ref "R27") (pin "1") (pinfunction "1_1") (pintype "passive"))
      (node (ref "R30") (pin "2") (pinfunction "2_2") (pintype "passive"))
      (node (ref "R33") (pin "1") (pinfunction "1_1") (pintype "passive"))
      (node (ref "R35") (pin "1") (pinfunction "1_1") (pintype "passive"))
      (node (ref "R37") (pin "2") (pinfunction "2_2") (pintype "passive"))
      (node (ref "R40") (pin "1") (pinfunction "1_1") (pintype "passive"))
      (node (ref "R43") (pin "1") (pinfunction "1_1") (pintype "passive"))
      (node (ref "R44") (pin "1") (pinfunction "1_1") (pintype "passive"))
      (node (ref "R47") (pin "1") (pinfunction "1_1") (pintype "passive"))
      (node (ref "R48") (pin "1") (pinfunction "1_1") (pintype "passive"))
      (node (ref "R51") (pin "1") (pinfunction "1_1") (pintype "passive"))
      (node (ref "R7") (pin "1") (pinfunction "1_1") (pintype "passive"))
      (node (ref "U1") (pin "8") (pinfunction "VCC_8") (pintype "bidirectional"))
      (node (ref "U2") (pin "8") (pinfunction "VCC33_8") (pintype "power_in"))
    )
    (net (code "4") (name "ANX_I2C_SCL") (class "Default")
      (node (ref "J8") (pin "9") (pinfunction "9_9") (pintype "bidirectional"))
    )
    (net (code "5") (name "ANX_I2C_SDA") (class "Default")
      (node (ref "J8") (pin "11") (pinfunction "11_11") (pintype "bidirectional"))
    )
    (net (code "6") (name "ANX_INTP") (class "Default")
      (node (ref "J8") (pin "12") (pinfunction "12_12") (pintype "bidirectional"))
    )
    (net (code "7") (name "AREF") (class "Default")
      (node (ref "C88") (pin "1") (pinfunction "1_1") (pintype "passive"))
      (node (ref "IC2") (pin "42") (pinfunction "AREF_42") (pintype "bidirectional"))
    )
    (net (code "8") (name "AV12") (class "Default")
      (node (ref "C103") (pin "1") (pinfunction "1_1") (pintype "passive"))
      (node (ref "C104") (pin "1") (pinfunction "1_1") (pintype "passive"))
      (node (ref "C33") (pin "1") (pinfunction "1_1") (pintype "passive"))
      (node (ref "C34") (pin "1") (pinfunction "1_1") (pintype "passive"))
      (node (ref "C35") (pin "1") (pinfunction "1_1") (pintype "passive"))
      (node (ref "C36") (pin "1") (pinfunction "1_1") (pintype "passive"))
      (node (ref "C37") (pin "1") (pinfunction "1_1") (pintype "passive"))
      (node (ref "IC1") (pin "13") (pinfunction "VP12_P4_13") (pintype "bidirectional"))
      (node (ref "IC1") (pin "3") (pinfunction "VP12_P3_3") (pintype "bidirectional"))
      (node (ref "IC1") (pin "40") (pinfunction "VP12_P0_40") (pintype "bidirectional"))
      (node (ref "IC1") (pin "46") (pinfunction "AVDD12_46") (pintype "bidirectional"))
      (node (ref "IC1") (pin "49") (pinfunction "VPP12_P1_49") (pintype "bidirectional"))
      (node (ref "IC1") (pin "58") (pinfunction "VP12_P2_58") (pintype "bidirectional"))
      (node (ref "L6") (pin "1") (pinfunction "1_1") (pintype "passive"))
    )
    (net (code "9") (name "AV33") (class "Default")
      (node (ref "C105") (pin "1") (pinfunction "1_1") (pintype "passive"))
      (node (ref "C63") (pin "1") (pinfunction "1_1") (pintype "passive"))
      (node (ref "C64") (pin "1") (pinfunction "1_1") (pintype "passive"))
      (node (ref "C65") (pin "1") (pinfunction "1_1") (pintype "passive"))
      (node (ref "IC1") (pin "35") (pinfunction "AVDD33_35") (pintype "bidirectional"))
      (node (ref "IC1") (pin "43") (pinfunction "AVDD33_43") (pintype "bidirectional"))
      (node (ref "IC1") (pin "54") (pinfunction "AVDD33_54") (pintype "bidirectional"))
      (node (ref "IC1") (pin "8") (pinfunction "AVDD33_8") (pintype "bidirectional"))
      (node (ref "L5") (pin "1") (pinfunction "1_1") (pintype "passive"))
    )
    (net (code "10") (name "BUS") (class "Default")
      (node (ref "D4") (pin "-") (pinfunction "-_-") (pintype "passive"))
      (node (ref "R5") (pin "1") (pinfunction "1_1") (pintype "passive"))
      (node (ref "USBC1") (pin "A4") (pinfunction "VBUS_A4") (pintype "passive"))
      (node (ref "USBC1") (pin "A9") (pinfunction "VBUS_A9") (pintype "passive"))
      (node (ref "USBC1") (pin "B4") (pinfunction "VBUS_B4") (pintype "passive"))
      (node (ref "USBC1") (pin "B9") (pinfunction "VBUS_B9") (pintype "passive"))
    )
    (net (code "11") (name "CC1") (class "Default")
      (node (ref "D5") (pin "4") (pinfunction "D2+_4") (pintype "passive"))
      (node (ref "D5") (pin "7") (pinfunction "NC_7") (pintype "passive"))
      (node (ref "U2") (pin "2") (pinfunction "CC1_2") (pintype "bidirectional"))
      (node (ref "USBC1") (pin "A5") (pinfunction "CC1_A5") (pintype "passive"))
    )
    (net (code "12") (name "CC2") (class "Default")
      (node (ref "D5") (pin "5") (pinfunction "D2-_5") (pintype "passive"))
      (node (ref "D5") (pin "6") (pinfunction "NC_6") (pintype "passive"))
      (node (ref "U2") (pin "1") (pinfunction "CC2_1") (pintype "bidirectional"))
      (node (ref "USBC1") (pin "B5") (pinfunction "CC2_B5") (pintype "passive"))
    )
    (net (code "13") (name "CLK-2") (class "Default")
      (node (ref "R24") (pin "1") (pinfunction "1_1") (pintype "passive"))
      (node (ref "U3") (pin "29") (pinfunction "S2CK_M2D0_29") (pintype "bidirectional"))
    )
    (net (code "14") (name "CMD-2") (class "Default")
      (node (ref "H1") (pin "M5") (pinfunction "CMD_M5") (pintype "bidirectional"))
      (node (ref "U3") (pin "30") (pinfunction "S2CM_M2D2_30") (pintype "bidirectional"))
    )
    (net (code "15") (name "CRX1_N") (class "Default")
      (node (ref "D1") (pin "2") (pinfunction "D1-_2") (pintype "passive"))
      (node (ref "D1") (pin "9") (pinfunction "NC_9") (pintype "passive"))
      (node (ref "U2") (pin "15") (pinfunction "RX1P_15") (pintype "bidirectional"))
      (node (ref "USBC1") (pin "B10") (pinfunction "SSRXN1_B10") (pintype "passive"))
    )
    (net (code "16") (name "CRX1_P") (class "Default")
      (node (ref "D1") (pin "1") (pinfunction "D1+_1") (pintype "passive"))
      (node (ref "D1") (pin "10") (pinfunction "NC_10") (pintype "passive"))
      (node (ref "U2") (pin "14") (pinfunction "RX1N_14") (pintype "bidirectional"))
      (node (ref "USBC1") (pin "B11") (pinfunction "SSRXP1_B11") (pintype "passive"))
    )
    (net (code "17") (name "CRX2_N") (class "Default")
      (node (ref "D2") (pin "1") (pinfunction "D1+_1") (pintype "passive"))
      (node (ref "D2") (pin "10") (pinfunction "NC_10") (pintype "passive"))
      (node (ref "U2") (pin "18") (pinfunction "RX2N_18") (pintype "bidirectional"))
      (node (ref "USBC1") (pin "A10") (pinfunction "SSRXN2_A10") (pintype "passive"))
    )
    (net (code "18") (name "CRX2_P") (class "Default")
      (node (ref "D2") (pin "2") (pinfunction "D1-_2") (pintype "passive"))
      (node (ref "D2") (pin "9") (pinfunction "NC_9") (pintype "passive"))
      (node (ref "U2") (pin "19") (pinfunction "RX2P_19") (pintype "bidirectional"))
      (node (ref "USBC1") (pin "A11") (pinfunction "SSRXP2_A11") (pintype "passive"))
    )
    (net (code "19") (name "CTX1_N") (class "Default")
      (node (ref "C5") (pin "1") (pinfunction "1_1") (pintype "passive"))
      (node (ref "D1") (pin "5") (pinfunction "D2-_5") (pintype "passive"))
      (node (ref "D1") (pin "6") (pinfunction "NC_6") (pintype "passive"))
      (node (ref "USBC1") (pin "A3") (pinfunction "SSTXN1_A3") (pintype "passive"))
    )
    (net (code "20") (name "CTX1_P") (class "Default")
      (node (ref "C6") (pin "1") (pinfunction "1_1") (pintype "passive"))
      (node (ref "D1") (pin "4") (pinfunction "D2+_4") (pintype "passive"))
      (node (ref "D1") (pin "7") (pinfunction "NC_7") (pintype "passive"))
      (node (ref "USBC1") (pin "A2") (pinfunction "SSTXP1_A2") (pintype "passive"))
    )
    (net (code "21") (name "CTX2_N") (class "Default")
      (node (ref "C7") (pin "1") (pinfunction "1_1") (pintype "passive"))
      (node (ref "D2") (pin "4") (pinfunction "D2+_4") (pintype "passive"))
      (node (ref "D2") (pin "7") (pinfunction "NC_7") (pintype "passive"))
      (node (ref "USBC1") (pin "B3") (pinfunction "SSTXN2_B3") (pintype "passive"))
    )
    (net (code "22") (name "CTX2_P") (class "Default")
      (node (ref "C8") (pin "1") (pinfunction "1_1") (pintype "passive"))
      (node (ref "D2") (pin "5") (pinfunction "D2-_5") (pintype "passive"))
      (node (ref "D2") (pin "6") (pinfunction "NC_6") (pintype "passive"))
      (node (ref "USBC1") (pin "B2") (pinfunction "SSTXP2_B2") (pintype "passive"))
    )
    (net (code "23") (name "DAT0-1") (class "Default")
      (node (ref "H1") (pin "B3") (pinfunction "DAT4_B3") (pintype "bidirectional"))
      (node (ref "U3") (pin "38") (pinfunction "S1D0_M1D1_38") (pintype "bidirectional"))
    )
    (net (code "24") (name "DAT0-2") (class "Default")
      (node (ref "H1") (pin "A3") (pinfunction "DAT0_A3") (pintype "bidirectional"))
      (node (ref "U3") (pin "28") (pinfunction "S2D0_M2D1_28") (pintype "bidirectional"))
    )
    (net (code "25") (name "DAT1-1") (class "Default")
      (node (ref "H1") (pin "B4") (pinfunction "DAT5_B4") (pintype "bidirectional"))
      (node (ref "U3") (pin "37") (pinfunction "S1D1_M1BS_37") (pintype "bidirectional"))
    )
    (net (code "26") (name "DAT1-2") (class "Default")
      (node (ref "H1") (pin "A4") (pinfunction "DAT1_A4") (pintype "bidirectional"))
      (node (ref "U3") (pin "27") (pinfunction "S2D1_M2BS_27") (pintype "bidirectional"))
    )
    (net (code "27") (name "DAT2-1") (class "Default")
      (node (ref "H1") (pin "B5") (pinfunction "DAT6_B5") (pintype "bidirectional"))
      (node (ref "U3") (pin "42") (pinfunction "S1D2_M1CK_42") (pintype "bidirectional"))
    )
    (net (code "28") (name "DAT2-2") (class "Default")
      (node (ref "H1") (pin "A5") (pinfunction "DAT2_A5") (pintype "bidirectional"))
      (node (ref "U3") (pin "32") (pinfunction "S2D2_M2CK_32") (pintype "bidirectional"))
    )
    (net (code "29") (name "DAT3-1") (class "Default")
      (node (ref "H1") (pin "B6") (pinfunction "DAT7_B6") (pintype "bidirectional"))
      (node (ref "U3") (pin "41") (pinfunction "S1D3_M1D3_41") (pintype "bidirectional"))
    )
    (net (code "30") (name "DAT3-2") (class "Default")
      (node (ref "H1") (pin "B2") (pinfunction "DAT3_B2") (pintype "bidirectional"))
      (node (ref "U3") (pin "31") (pinfunction "S2D3_M2D3_31") (pintype "bidirectional"))
    )
    (net (code "31") (name "DIR") (class "Default")
      (node (ref "R16") (pin "1") (pinfunction "1_1") (pintype "passive"))
      (node (ref "U2") (pin "11") (pinfunction "DIR_11") (pintype "open_collector"))
    )
    (net (code "32") (name "DS1D_N") (class "Default")
      (node (ref "IC1") (pin "53") (pinfunction "DM_P1_53") (pintype "bidirectional"))
      (node (ref "J1") (pin "4") (pinfunction "4_4") (pintype "bidirectional"))
    )
    (net (code "33") (name "DS1D_P") (class "Default")
      (node (ref "IC1") (pin "52") (pinfunction "DP_P1_52") (pintype "bidirectional"))
      (node (ref "J1") (pin "3") (pinfunction "3_3") (pintype "bidirectional"))
    )
    (net (code "34") (name "DS2D_N") (class "Default")
      (node (ref "IC1") (pin "64") (pinfunction "DM_P2_64") (pintype "bidirectional"))
      (node (ref "R28") (pin "1") (pinfunction "1_1") (pintype "passive"))
    )
    (net (code "35") (name "DS2D_P") (class "Default")
      (node (ref "IC1") (pin "63") (pinfunction "DP_P2_63") (pintype "bidirectional"))
      (node (ref "R29") (pin "1") (pinfunction "1_1") (pintype "passive"))
    )
    (net (code "36") (name "DS2RX_N") (class "Default")
      (node (ref "C41") (pin "1") (pinfunction "1_1") (pintype "passive"))
      (node (ref "IC1") (pin "60") (pinfunction "RXP1_P2_60") (pintype "bidirectional"))
    )
    (net (code "37") (name "DS2RX_P") (class "Default")
      (node (ref "C42") (pin "1") (pinfunction "1_1") (pintype "passive"))
      (node (ref "IC1") (pin "59") (pinfunction "RXN1_P2_59") (pintype "bidirectional"))
    )
    (net (code "38") (name "DS2TX_N") (class "Default")
      (node (ref "C48") (pin "2") (pinfunction "2_2") (pintype "passive"))
      (node (ref "IC1") (pin "56") (pinfunction "TXN1_P2_56") (pintype "bidirectional"))
    )
    (net (code "39") (name "DS2TX_P") (class "Default")
      (node (ref "C43") (pin "2") (pinfunction "2_2") (pintype "passive"))
      (node (ref "IC1") (pin "57") (pinfunction "TXP1_P2_57") (pintype "bidirectional"))
    )
    (net (code "40") (name "DS2_RX_N") (class "Default")
      (node (ref "C41") (pin "2") (pinfunction "2_2") (pintype "passive"))
      (node (ref "U3") (pin "7") (pinfunction "TXN_7") (pintype "bidirectional"))
    )
    (net (code "41") (name "DS2_RX_P") (class "Default")
      (node (ref "C42") (pin "2") (pinfunction "2_2") (pintype "passive"))
      (node (ref "U3") (pin "8") (pinfunction "TXP_8") (pintype "bidirectional"))
    )
    (net (code "42") (name "DS2_TX_N") (class "Default")
      (node (ref "C43") (pin "1") (pinfunction "1_1") (pintype "passive"))
      (node (ref "U3") (pin "10") (pinfunction "RXN_10") (pintype "bidirectional"))
    )
    (net (code "43") (name "DS2_TX_P") (class "Default")
      (node (ref "C48") (pin "1") (pinfunction "1_1") (pintype "passive"))
      (node (ref "U3") (pin "11") (pinfunction "RXP_11") (pintype "bidirectional"))
    )
    (net (code "44") (name "DS3D_N") (class "Default")
      (node (ref "IC1") (pin "7") (pinfunction "DM_P3_7") (pintype "bidirectional"))
      (node (ref "J3") (pin "4") (pinfunction "4_4") (pintype "bidirectional"))
    )
    (net (code "45") (name "DS3D_P") (class "Default")
      (node (ref "IC1") (pin "6") (pinfunction "DP_P3_6") (pintype "bidirectional"))
      (node (ref "J3") (pin "5") (pinfunction "5_5") (pintype "bidirectional"))
    )
    (net (code "46") (name "DS3RX_N") (class "Default")
      (node (ref "IC1") (pin "4") (pinfunction "RXN1_P3_4") (pintype "bidirectional"))
      (node (ref "J3") (pin "10") (pinfunction "10_10") (pintype "bidirectional"))
    )
    (net (code "47") (name "DS3RX_P") (class "Default")
      (node (ref "IC1") (pin "5") (pinfunction "RXP1_P3_5") (pintype "bidirectional"))
      (node (ref "J3") (pin "11") (pinfunction "11_11") (pintype "bidirectional"))
    )
    (net (code "48") (name "DS3TX_N") (class "Default")
      (node (ref "C16") (pin "1") (pinfunction "1_1") (pintype "passive"))
      (node (ref "IC1") (pin "1") (pinfunction "TXN1_P3_1") (pintype "bidirectional"))
    )
    (net (code "49") (name "DS3TX_P") (class "Default")
      (node (ref "C15") (pin "1") (pinfunction "1_1") (pintype "passive"))
      (node (ref "IC1") (pin "2") (pinfunction "TXP1_P3_2") (pintype "bidirectional"))
    )
    (net (code "50") (name "DS4D_N") (class "Default")
      (node (ref "IC1") (pin "10") (pinfunction "DM_P4_10") (pintype "bidirectional"))
      (node (ref "J9") (pin "4") (pinfunction "4_4") (pintype "bidirectional"))
    )
    (net (code "51") (name "DS4D_P") (class "Default")
      (node (ref "IC1") (pin "9") (pinfunction "DP_P4_9") (pintype "bidirectional"))
      (node (ref "J9") (pin "5") (pinfunction "5_5") (pintype "bidirectional"))
    )
    (net (code "52") (name "DS4RX_N") (class "Default")
      (node (ref "IC1") (pin "14") (pinfunction "RXN1_P4_14") (pintype "bidirectional"))
      (node (ref "J9") (pin "10") (pinfunction "10_10") (pintype "bidirectional"))
    )
    (net (code "53") (name "DS4RX_P") (class "Default")
      (node (ref "IC1") (pin "15") (pinfunction "RXP1_P4_15") (pintype "bidirectional"))
      (node (ref "J9") (pin "11") (pinfunction "11_11") (pintype "bidirectional"))
    )
    (net (code "54") (name "DS4TXE_N") (class "Default")
      (node (ref "C3") (pin "2") (pinfunction "2_2") (pintype "passive"))
      (node (ref "J9") (pin "7") (pinfunction "7_7") (pintype "bidirectional"))
    )
    (net (code "55") (name "DS4TXE_P") (class "Default")
      (node (ref "C4") (pin "2") (pinfunction "2_2") (pintype "passive"))
      (node (ref "J9") (pin "8") (pinfunction "8_8") (pintype "bidirectional"))
    )
    (net (code "56") (name "DS4TX_N") (class "Default")
      (node (ref "C3") (pin "1") (pinfunction "1_1") (pintype "passive"))
      (node (ref "IC1") (pin "11") (pinfunction "TXN1_P4_11") (pintype "bidirectional"))
    )
    (net (code "57") (name "DS4TX_P") (class "Default")
      (node (ref "C4") (pin "1") (pinfunction "1_1") (pintype "passive"))
      (node (ref "IC1") (pin "12") (pinfunction "TXP1_P4_12") (pintype "bidirectional"))
    )
    (net (code "58") (name "DVDD12") (class "Default")
      (node (ref "C75") (pin "2") (pinfunction "2_2") (pintype "passive"))
      (node (ref "C83") (pin "2") (pinfunction "2_2") (pintype "passive"))
      (node (ref "U3") (pin "26") (pinfunction "DVDD12_26") (pintype "bidirectional"))
      (node (ref "U3") (pin "9") (pinfunction "AVDD12_9") (pintype "bidirectional"))
    )
    (net (code "59") (name "DVDD33") (class "Default")
      (node (ref "C50") (pin "2") (pinfunction "2_2") (pintype "passive"))
      (node (ref "C73") (pin "2") (pinfunction "2_2") (pintype "passive"))
      (node (ref "C78") (pin "2") (pinfunction "2_2") (pintype "passive"))
      (node (ref "C79") (pin "2") (pinfunction "2_2") (pintype "passive"))
      (node (ref "C80") (pin "2") (pinfunction "2_2") (pintype "passive"))
      (node (ref "C99") (pin "2") (pinfunction "2_2") (pintype "passive"))
      (node (ref "H1") (pin "E6") (pinfunction "VCC_1_E6") (pintype "bidirectional"))
      (node (ref "H1") (pin "F5") (pinfunction "VCC_2_F5") (pintype "bidirectional"))
      (node (ref "H1") (pin "J10") (pinfunction "VCC_3_J10") (pintype "bidirectional"))
      (node (ref "H1") (pin "K9") (pinfunction "VCC_4_K9") (pintype "bidirectional"))
      (node (ref "U3") (pin "15") (pinfunction "AVDD33_15") (pintype "bidirectional"))
      (node (ref "U3") (pin "23") (pinfunction "S1M1_VCC_23") (pintype "bidirectional"))
      (node (ref "U3") (pin "25") (pinfunction "DVDD33_25") (pintype "bidirectional"))
      (node (ref "U3") (pin "34") (pinfunction "DVDD33_34") (pintype "bidirectional"))
      (node (ref "U3") (pin "44") (pinfunction "DVDD33_44") (pintype "bidirectional"))
      (node (ref "U3") (pin "6") (pinfunction "AVDD33_6") (pintype "bidirectional"))
    )
    (net (code "60") (name "D_N") (class "Default")
      (node (ref "IC2") (pin "3") (pinfunction "D-_3") (pintype "bidirectional"))
      (node (ref "R28") (pin "2") (pinfunction "2_2") (pintype "passive"))
    )
    (net (code "61") (name "D_P") (class "Default")
      (node (ref "IC2") (pin "4") (pinfunction "D+_4") (pintype "bidirectional"))
      (node (ref "R29") (pin "2") (pinfunction "2_2") (pintype "passive"))
    )
    (net (code "62") (name "D_UP_N") (class "Default")
      (node (ref "D5") (pin "1") (pinfunction "D1+_1") (pintype "passive"))
      (node (ref "D5") (pin "10") (pinfunction "NC_10") (pintype "passive"))
      (node (ref "IC1") (pin "36") (pinfunction "DM_P0_36") (pintype "bidirectional"))
      (node (ref "USBC1") (pin "A7") (pinfunction "DN1_A7") (pintype "passive"))
      (node (ref "USBC1") (pin "B7") (pinfunction "DN2_B7") (pintype "passive"))
    )
    (net (code "63") (name "D_UP_P") (class "Default")
      (node (ref "D5") (pin "2") (pinfunction "D1-_2") (pintype "passive"))
      (node (ref "D5") (pin "9") (pinfunction "NC_9") (pintype "passive"))
      (node (ref "IC1") (pin "37") (pinfunction "DP_P0_37") (pintype "bidirectional"))
      (node (ref "USBC1") (pin "A6") (pinfunction "DP1_A6") (pintype "passive"))
      (node (ref "USBC1") (pin "B6") (pinfunction "DP2_B6") (pintype "passive"))
    )
    (net (code "64") (name "EMMC_RST-2") (class "Default")
      (node (ref "C71") (pin "2") (pinfunction "2_2") (pintype "passive"))
      (node (ref "H1") (pin "K5") (pinfunction "RST__N_K5") (pintype "bidirectional"))
      (node (ref "R25") (pin "2") (pinfunction "2_2") (pintype "passive"))
      (node (ref "U3") (pin "36") (pinfunction "SD2_CDZ_36") (pintype "bidirectional"))
    )
    (net (code "65") (name "EN1") (class "Default")
      (node (ref "IC2") (pin "28") (pinfunction "PB4_(PCINT4/ADC11)_28") (pintype "bidirectional"))
      (node (ref "R38") (pin "1") (pinfunction "1_1") (pintype "passive"))
      (node (ref "U6") (pin "4") (pinfunction "EN/~{EN}_4") (pintype "bidirectional"))
    )
    (net (code "66") (name "EN2") (class "Default")
      (node (ref "IC2") (pin "26") (pinfunction "PD6_(T1/~{OC4D}/ADC9)_26") (pintype "bidirectional"))
      (node (ref "R41") (pin "2") (pinfunction "2_2") (pintype "passive"))
      (node (ref "U7") (pin "4") (pinfunction "EN/~{EN}_4") (pintype "bidirectional"))
    )
    (net (code "67") (name "EN3") (class "Default")
      (node (ref "IC2") (pin "31") (pinfunction "PC6_(OC3A/~{OC4A})_31") (pintype "bidirectional"))
      (node (ref "R35") (pin "2") (pinfunction "2_2") (pintype "passive"))
      (node (ref "U8") (pin "4") (pinfunction "EN/~{EN}_4") (pintype "bidirectional"))
    )
    (net (code "68") (name "FAN_PWM") (class "Default")
      (node (ref "IC2") (pin "30") (pinfunction "PB6_(PCINT6/OC1B/OC4B/ADC13)_30") (pintype "bidirectional"))
      (node (ref "Q2") (pin "1") (pinfunction "INPUT_1") (pintype "passive"))
    )
    (net (code "69") (name "FN_A") (class "Default")
      (node (ref "IC1") (pin "22") (pinfunction "FN_A_22") (pintype "bidirectional"))
      (node (ref "R43") (pin "2") (pinfunction "2_2") (pintype "passive"))
    )
    (net (code "70") (name "FN_B") (class "Default")
      (node (ref "IC1") (pin "23") (pinfunction "FN_B_23") (pintype "bidirectional"))
      (node (ref "R44") (pin "2") (pinfunction "2_2") (pintype "passive"))
    )
    (net (code "71") (name "GND") (class "Default")
      (node (ref "C1") (pin "2") (pinfunction "2_2") (pintype "passive"))
      (node (ref "C10") (pin "1") (pinfunction "1_1") (pintype "passive"))
      (node (ref "C100") (pin "1") (pinfunction "1_1") (pintype "passive"))
      (node (ref "C101") (pin "2") (pinfunction "2_2") (pintype "passive"))
      (node (ref "C102") (pin "2") (pinfunction "2_2") (pintype "passive"))
      (node (ref "C103") (pin "2") (pinfunction "2_2") (pintype "passive"))
      (node (ref "C104") (pin "2") (pinfunction "2_2") (pintype "passive"))
      (node (ref "C105") (pin "2") (pinfunction "2_2") (pintype "passive"))
      (node (ref "C106") (pin "2") (pinfunction "2_2") (pintype "passive"))
      (node (ref "C12") (pin "1") (pinfunction "1_1") (pintype "passive"))
      (node (ref "C13") (pin "1") (pinfunction "1_1") (pintype "passive"))
      (node (ref "C14") (pin "1") (pinfunction "1_1") (pintype "passive"))
      (node (ref "C17") (pin "2") (pinfunction "2_2") (pintype "passive"))
      (node (ref "C18") (pin "1") (pinfunction "1_1") (pintype "passive"))
      (node (ref "C19") (pin "2") (pinfunction "2_2") (pintype "passive"))
      (node (ref "C20") (pin "1") (pinfunction "1_1") (pintype "passive"))
      (node (ref "C21") (pin "2") (pinfunction "2_2") (pintype "passive"))
      (node (ref "C22") (pin "2") (pinfunction "2_2") (pintype "passive"))
      (node (ref "C23") (pin "1") (pinfunction "1_1") (pintype "passive"))
      (node (ref "C24") (pin "2") (pinfunction "2_2") (pintype "passive"))
      (node (ref "C25") (pin "2") (pinfunction "2_2") (pintype "passive"))
      (node (ref "C26") (pin "1") (pinfunction "1_1") (pintype "passive"))
      (node (ref "C27") (pin "1") (pinfunction "1_1") (pintype "passive"))
      (node (ref "C28") (pin "1") (pinfunction "1_1") (pintype "passive"))
      (node (ref "C29") (pin "2") (pinfunction "2_2") (pintype "passive"))
      (node (ref "C30") (pin "2") (pinfunction "2_2") (pintype "passive"))
      (node (ref "C31") (pin "2") (pinfunction "2_2") (pintype "passive"))
      (node (ref "C32") (pin "1") (pinfunction "1_1") (pintype "passive"))
      (node (ref "C33") (pin "2") (pinfunction "2_2") (pintype "passive"))
      (node (ref "C34") (pin "2") (pinfunction "2_2") (pintype "passive"))
      (node (ref "C35") (pin "2") (pinfunction "2_2") (pintype "passive"))
      (node (ref "C36") (pin "2") (pinfunction "2_2") (pintype "passive"))
      (node (ref "C37") (pin "2") (pinfunction "2_2") (pintype "passive"))
      (node (ref "C38") (pin "1") (pinfunction "1_1") (pintype "passive"))
      (node (ref "C39") (pin "1") (pinfunction "1_1") (pintype "passive"))
      (node (ref "C40") (pin "1") (pinfunction "1_1") (pintype "passive"))
      (node (ref "C44") (pin "2") (pinfunction "2_2") (pintype "passive"))
      (node (ref "C45") (pin "1") (pinfunction "1_1") (pintype "passive"))
      (node (ref "C46") (pin "1") (pinfunction "1_1") (pintype "passive"))
      (node (ref "C47") (pin "1") (pinfunction "1_1") (pintype "passive"))
      (node (ref "C49") (pin "2") (pinfunction "2_2") (pintype "passive"))
      (node (ref "C50") (pin "1") (pinfunction "1_1") (pintype "passive"))
      (node (ref "C51") (pin "1") (pinfunction "1_1") (pintype "passive"))
      (node (ref "C52") (pin "2") (pinfunction "2_2") (pintype "passive"))
      (node (ref "C53") (pin "1") (pinfunction "1_1") (pintype "passive"))
      (node (ref "C54") (pin "1") (pinfunction "1_1") (pintype "passive"))
      (node (ref "C55") (pin "1") (pinfunction "1_1") (pintype "passive"))
      (node (ref "C56") (pin "1") (pinfunction "1_1") (pintype "passive"))
      (node (ref "C57") (pin "1") (pinfunction "1_1") (pintype "passive"))
      (node (ref "C59") (pin "2") (pinfunction "2_2") (pintype "passive"))
      (node (ref "C60") (pin "2") (pinfunction "2_2") (pintype "passive"))
      (node (ref "C61") (pin "2") (pinfunction "2_2") (pintype "passive"))
      (node (ref "C62") (pin "1") (pinfunction "1_1") (pintype "passive"))
      (node (ref "C63") (pin "2") (pinfunction "2_2") (pintype "passive"))
      (node (ref "C64") (pin "2") (pinfunction "2_2") (pintype "passive"))
      (node (ref "C65") (pin "2") (pinfunction "2_2") (pintype "passive"))
      (node (ref "C66") (pin "1") (pinfunction "1_1") (pintype "passive"))
      (node (ref "C67") (pin "2") (pinfunction "2_2") (pintype "passive"))
      (node (ref "C68") (pin "2") (pinfunction "2_2") (pintype "passive"))
      (node (ref "C71") (pin "1") (pinfunction "1_1") (pintype "passive"))
      (node (ref "C72") (pin "1") (pinfunction "1_1") (pintype "passive"))
      (node (ref "C73") (pin "1") (pinfunction "1_1") (pintype "passive"))
      (node (ref "C74") (pin "1") (pinfunction "1_1") (pintype "passive"))
      (node (ref "C75") (pin "1") (pinfunction "1_1") (pintype "passive"))
      (node (ref "C76") (pin "2") (pinfunction "2_2") (pintype "passive"))
      (node (ref "C77") (pin "2") (pinfunction "2_2") (pintype "passive"))
      (node (ref "C78") (pin "1") (pinfunction "1_1") (pintype "passive"))
      (node (ref "C79") (pin "1") (pinfunction "1_1") (pintype "passive"))
      (node (ref "C80") (pin "1") (pinfunction "1_1") (pintype "passive"))
      (node (ref "C81") (pin "1") (pinfunction "1_1") (pintype "passive"))
      (node (ref "C82") (pin "1") (pinfunction "1_1") (pintype "passive"))
      (node (ref "C83") (pin "1") (pinfunction "1_1") (pintype "passive"))
      (node (ref "C84") (pin "1") (pinfunction "1_1") (pintype "passive"))
      (node (ref "C85") (pin "2") (pinfunction "2_2") (pintype "passive"))
      (node (ref "C86") (pin "1") (pinfunction "1_1") (pintype "passive"))
      (node (ref "C87") (pin "1") (pinfunction "1_1") (pintype "passive"))
      (node (ref "C88") (pin "2") (pinfunction "2_2") (pintype "passive"))
      (node (ref "C89") (pin "2") (pinfunction "2_2") (pintype "passive"))
      (node (ref "C9") (pin "1") (pinfunction "1_1") (pintype "passive"))
      (node (ref "C90") (pin "2") (pinfunction "2_2") (pintype "passive"))
      (node (ref "C91") (pin "2") (pinfunction "2_2") (pintype "passive"))
      (node (ref "C92") (pin "2") (pinfunction "2_2") (pintype "passive"))
      (node (ref "C93") (pin "2") (pinfunction "2_2") (pintype "passive"))
      (node (ref "C94") (pin "2") (pinfunction "2_2") (pintype "passive"))
      (node (ref "C95") (pin "2") (pinfunction "2_2") (pintype "passive"))
      (node (ref "C96") (pin "1") (pinfunction "1_1") (pintype "passive"))
      (node (ref "C97") (pin "1") (pinfunction "1_1") (pintype "passive"))
      (node (ref "C98") (pin "1") (pinfunction "1_1") (pintype "passive"))
      (node (ref "C99") (pin "1") (pinfunction "1_1") (pintype "passive"))
      (node (ref "D1") (pin "3") (pinfunction "GND_3") (pintype "passive"))
      (node (ref "D1") (pin "8") (pinfunction "GND_8") (pintype "passive"))
      (node (ref "D2") (pin "3") (pinfunction "GND_3") (pintype "passive"))
      (node (ref "D2") (pin "8") (pinfunction "GND_8") (pintype "passive"))
      (node (ref "D3") (pin "2") (pinfunction "-_2") (pintype "passive"))
      (node (ref "D4") (pin "+") (pinfunction "+_+") (pintype "passive"))
      (node (ref "D5") (pin "3") (pinfunction "GND_3") (pintype "passive"))
      (node (ref "D5") (pin "8") (pinfunction "GND_8") (pintype "passive"))
      (node (ref "D6") (pin "2") (pinfunction "-_2") (pintype "passive"))
      (node (ref "D7") (pin "+") (pinfunction "A_+") (pintype "passive"))
      (node (ref "H1") (pin "A6") (pinfunction "VSS_1_A6") (pintype "bidirectional"))
      (node (ref "H1") (pin "C4") (pinfunction "VSSQ_1_C4") (pintype "bidirectional"))
      (node (ref "H1") (pin "E7") (pinfunction "VSS_2_E7") (pintype "bidirectional"))
      (node (ref "H1") (pin "G5") (pinfunction "VSS_3_G5") (pintype "bidirectional"))
      (node (ref "H1") (pin "H10") (pinfunction "VSS_4_H10") (pintype "bidirectional"))
      (node (ref "H1") (pin "J5") (pinfunction "VSS_5_J5") (pintype "bidirectional"))
      (node (ref "H1") (pin "K8") (pinfunction "VSS_6_K8") (pintype "bidirectional"))
      (node (ref "H1") (pin "N2") (pinfunction "VSSQ_2_N2") (pintype "bidirectional"))
      (node (ref "H1") (pin "N5") (pinfunction "VSSQ_3_N5") (pintype "bidirectional"))
      (node (ref "H1") (pin "P4") (pinfunction "VSSQ_4_P4") (pintype "bidirectional"))
      (node (ref "H1") (pin "P6") (pinfunction "VSSQ_5_P6") (pintype "bidirectional"))
      (node (ref "IC1") (pin "65") (pinfunction "PAD_65") (pintype "bidirectional"))
      (node (ref "IC2") (pin "15") (pinfunction "GND_1_15") (pintype "bidirectional"))
      (node (ref "IC2") (pin "23") (pinfunction "GND_2_23") (pintype "bidirectional"))
      (node (ref "IC2") (pin "35") (pinfunction "GND_3_35") (pintype "bidirectional"))
      (node (ref "IC2") (pin "43") (pinfunction "GND_4_43") (pintype "bidirectional"))
      (node (ref "IC2") (pin "45") (pinfunction "GND_5_45") (pintype "bidirectional"))
      (node (ref "IC2") (pin "5") (pinfunction "UGND_5") (pintype "bidirectional"))
      (node (ref "J1") (pin "1") (pinfunction "1_1") (pintype "bidirectional"))
      (node (ref "J1") (pin "2") (pinfunction "2_2") (pintype "bidirectional"))
      (node (ref "J10") (pin "4") (pinfunction "4_4") (pintype "bidirectional"))
      (node (ref "J3") (pin "12") (pinfunction "12_12") (pintype "bidirectional"))
      (node (ref "J3") (pin "3") (pinfunction "3_3") (pintype "bidirectional"))
      (node (ref "J3") (pin "6") (pinfunction "6_6") (pintype "bidirectional"))
      (node (ref "J3") (pin "9") (pinfunction "9_9") (pintype "bidirectional"))
      (node (ref "J4") (pin "1") (pinfunction "1_1") (pintype "bidirectional"))
      (node (ref "J5") (pin "1") (pinfunction "S_1") (pintype "passive"))
      (node (ref "J6") (pin "1") (pinfunction "S_1") (pintype "passive"))
      (node (ref "J7") (pin "2") (pinfunction "2_2") (pintype "bidirectional"))
      (node (ref "J8") (pin "10") (pinfunction "10_10") (pintype "bidirectional"))
      (node (ref "J8") (pin "2") (pinfunction "2_2") (pintype "bidirectional"))
      (node (ref "J8") (pin "8") (pinfunction "8_8") (pintype "bidirectional"))
      (node (ref "J9") (pin "12") (pinfunction "12_12") (pintype "bidirectional"))
      (node (ref "J9") (pin "3") (pinfunction "3_3") (pintype "bidirectional"))
      (node (ref "J9") (pin "6") (pinfunction "6_6") (pintype "bidirectional"))
      (node (ref "J9") (pin "9") (pinfunction "9_9") (pintype "bidirectional"))
      (node (ref "K1") (pin "2") (pinfunction "2_2") (pintype "bidirectional"))
      (node (ref "Q2") (pin "2") (pinfunction "E_2") (pintype "passive"))
      (node (ref "R13") (pin "2") (pinfunction "2_2") (pintype "passive"))
      (node (ref "R2") (pin "2") (pinfunction "2_2") (pintype "passive"))
      (node (ref "R21") (pin "1") (pinfunction "1_1") (pintype "passive"))
      (node (ref "R22") (pin "1") (pinfunction "1_1") (pintype "passive"))
      (node (ref "R39") (pin "1") (pinfunction "1_1") (pintype "passive"))
      (node (ref "R4") (pin "1") (pinfunction "1_1") (pintype "passive"))
      (node (ref "R42") (pin "1") (pinfunction "1_1") (pintype "passive"))
      (node (ref "R45") (pin "1") (pinfunction "1_1") (pintype "passive"))
      (node (ref "R9") (pin "2") (pinfunction "2_2") (pintype "passive"))
      (node (ref "RT1") (pin "2") (pinfunction "2_2") (pintype "bidirectional"))
      (node (ref "U1") (pin "4") (pinfunction "GND_4") (pintype "bidirectional"))
      (node (ref "U2") (pin "12") (pinfunction "EN_MUX_N_12") (pintype "input"))
      (node (ref "U2") (pin "13") (pinfunction "GND_2_13") (pintype "power_in"))
      (node (ref "U2") (pin "28") (pinfunction "GND_28") (pintype "power_in"))
      (node (ref "U2") (pin "29") (pinfunction "EN_CC_N_29") (pintype "input"))
      (node (ref "U2") (pin "31") (pinfunction "PAD_31") (pintype "power_in"))
      (node (ref "U2") (pin "4") (pinfunction "PORT_4") (pintype "input"))
      (node (ref "U3") (pin "12") (pinfunction "GND_12") (pintype "bidirectional"))
      (node (ref "U3") (pin "3") (pinfunction "GND_3") (pintype "bidirectional"))
      (node (ref "U3") (pin "35") (pinfunction "MS2_INS/SD2_WP_35") (pintype "bidirectional"))
      (node (ref "U3") (pin "THERMAL") (pinfunction "THERMAL_THERMAL") (pintype "bidirectional"))
      (node (ref "U4") (pin "2") (pinfunction "GND_2") (pintype "bidirectional"))
      (node (ref "U5") (pin "2") (pinfunction "GND_2") (pintype "bidirectional"))
      (node (ref "U6") (pin "2") (pinfunction "GND_2") (pintype "bidirectional"))
      (node (ref "U7") (pin "2") (pinfunction "GND_2") (pintype "bidirectional"))
      (node (ref "U8") (pin "2") (pinfunction "GND_2") (pintype "bidirectional"))
      (node (ref "USBC1") (pin "0") (pinfunction "0_0") (pintype "passive"))
      (node (ref "USBC1") (pin "0-1") (pinfunction "0_0-1") (pintype "passive"))
      (node (ref "USBC1") (pin "0-2") (pinfunction "0_0-2") (pintype "passive"))
      (node (ref "USBC1") (pin "0-3") (pinfunction "0_0-3") (pintype "passive"))
      (node (ref "USBC1") (pin "0-4") (pinfunction "0_0-4") (pintype "passive"))
      (node (ref "USBC1") (pin "0-5") (pinfunction "0_0-5") (pintype "passive"))
      (node (ref "USBC1") (pin "0-6") (pinfunction "0_0-6") (pintype "passive"))
      (node (ref "USBC1") (pin "0-7") (pinfunction "0_0-7") (pintype "passive"))
      (node (ref "USBC1") (pin "0-8") (pinfunction "0_0-8") (pintype "passive"))
      (node (ref "USBC1") (pin "0-9") (pinfunction "0_0-9") (pintype "passive"))
      (node (ref "USBC1") (pin "1") (pinfunction "0_1") (pintype "passive"))
      (node (ref "USBC1") (pin "2") (pinfunction "0_2") (pintype "passive"))
      (node (ref "USBC1") (pin "A1") (pinfunction "GND_A1") (pintype "passive"))
      (node (ref "USBC1") (pin "A12") (pinfunction "GND_A12") (pintype "passive"))
      (node (ref "USBC1") (pin "B1") (pinfunction "GND_B1") (pintype "passive"))
      (node (ref "USBC1") (pin "B12") (pinfunction "GND_B12") (pintype "passive"))
      (node (ref "X1") (pin "1") (pinfunction "1NC_1") (pintype "bidirectional"))
      (node (ref "X1") (pin "3") (pinfunction "3NC_3") (pintype "bidirectional"))
      (node (ref "X3") (pin "1") (pinfunction "1NC_1") (pintype "bidirectional"))
      (node (ref "X3") (pin "3") (pinfunction "3NC_3") (pintype "bidirectional"))
      (node (ref "X4") (pin "1") (pinfunction "1NC_1") (pintype "bidirectional"))
      (node (ref "X4") (pin "3") (pinfunction "3NC_3") (pintype "bidirectional"))
    )
    (net (code "72") (name "INT") (class "Default")
      (node (ref "IC2") (pin "1") (pinfunction "(INT.6/AIN0)_PE6_1") (pintype "bidirectional"))
      (node (ref "J7") (pin "1") (pinfunction "1_1") (pintype "bidirectional"))
    )
    (net (code "73") (name "LED") (class "Default")
      (node (ref "IC2") (pin "32") (pinfunction "PC7_(ICP3/CLK0/OC4A)_32") (pintype "bidirectional"))
      (node (ref "R32") (pin "1") (pinfunction "1_1") (pintype "passive"))
    )
    (net (code "74") (name "MCU_EXT2_TX") (class "Default")
      (node (ref "J8") (pin "7") (pinfunction "7_7") (pintype "bidirectional"))
      (node (ref "Q4") (pin "2") (pinfunction "S_2") (pintype "passive"))
      (node (ref "R50") (pin "2") (pinfunction "2_2") (pintype "passive"))
    )
    (net (code "75") (name "MCU_EXT3_RX") (class "Default")
      (node (ref "J8") (pin "6") (pinfunction "6_6") (pintype "bidirectional"))
      (node (ref "Q3") (pin "2") (pinfunction "S_2") (pintype "passive"))
      (node (ref "R49") (pin "2") (pinfunction "2_2") (pintype "passive"))
    )
    (net (code "76") (name "MCU_SWD_CLK") (class "Default")
      (node (ref "J8") (pin "4") (pinfunction "4_4") (pintype "bidirectional"))
    )
    (net (code "77") (name "MCU_SWD_IO") (class "Default")
      (node (ref "J8") (pin "5") (pinfunction "5_5") (pintype "bidirectional"))
    )
    (net (code "78") (name "MCU_SWD_RST") (class "Default")
      (node (ref "IC2") (pin "12") (pinfunction "(PCINT7/OC0A/OC1C/~{RTS})_PB7_12") (pintype "bidirectional"))
      (node (ref "J8") (pin "3") (pinfunction "3_3") (pintype "bidirectional"))
    )
    (net (code "79") (name "MISO") (class "Default")
      (node (ref "IC2") (pin "11") (pinfunction "(PDO/PCINT3/MISO)_PB3_11") (pintype "bidirectional"))
      (node (ref "J10") (pin "1") (pinfunction "1_1") (pintype "bidirectional"))
    )
    (net (code "80") (name "MOSI") (class "Default")
      (node (ref "IC2") (pin "10") (pinfunction "(PDI/PCINT2/MOSI)_PB2_10") (pintype "bidirectional"))
      (node (ref "J10") (pin "5") (pinfunction "5_5") (pintype "bidirectional"))
    )
    (net (code "81") (name "Net-(C87-Pad2)") (class "Default")
      (node (ref "C87") (pin "2") (pinfunction "2_2") (pintype "passive"))
      (node (ref "R37") (pin "1") (pinfunction "1_1") (pintype "passive"))
      (node (ref "R38") (pin "2") (pinfunction "2_2") (pintype "passive"))
    )
    (net (code "82") (name "Net-(C98-Pad2)") (class "Default")
      (node (ref "C98") (pin "2") (pinfunction "2_2") (pintype "passive"))
      (node (ref "R41") (pin "1") (pinfunction "1_1") (pintype "passive"))
      (node (ref "R7") (pin "2") (pinfunction "2_2") (pintype "passive"))
    )
    (net (code "83") (name "Net-(D3-+)") (class "Default")
      (node (ref "D3") (pin "1") (pinfunction "+_1") (pintype "passive"))
      (node (ref "R23") (pin "2") (pinfunction "2_2") (pintype "passive"))
    )
    (net (code "84") (name "Net-(D6-+)") (class "Default")
      (node (ref "D6") (pin "1") (pinfunction "+_1") (pintype "passive"))
      (node (ref "R32") (pin "2") (pinfunction "2_2") (pintype "passive"))
    )
    (net (code "85") (name "Net-(D7-C)") (class "Default")
      (node (ref "C100") (pin "2") (pinfunction "2_2") (pintype "passive"))
      (node (ref "D7") (pin "-") (pinfunction "C_-") (pintype "passive"))
      (node (ref "J5") (pin "2") (pinfunction "S_2") (pintype "passive"))
      (node (ref "Q1") (pin "3") (pinfunction "D_3") (pintype "passive"))
    )
    (net (code "86") (name "Net-(H1-CLK)") (class "Default")
      (node (ref "H1") (pin "M6") (pinfunction "CLK_M6") (pintype "bidirectional"))
      (node (ref "R24") (pin "2") (pinfunction "2_2") (pintype "passive"))
    )
    (net (code "87") (name "Net-(H1-VDDI)") (class "Default")
      (node (ref "C72") (pin "2") (pinfunction "2_2") (pintype "passive"))
      (node (ref "H1") (pin "C2") (pinfunction "VDDI_C2") (pintype "bidirectional"))
    )
    (net (code "88") (name "Net-(IC1-FB)") (class "Default")
      (node (ref "C106") (pin "1") (pinfunction "1_1") (pintype "passive"))
      (node (ref "IC1") (pin "17") (pinfunction "FB_17") (pintype "bidirectional"))
      (node (ref "R46") (pin "2") (pinfunction "2_2") (pintype "passive"))
    )
    (net (code "89") (name "Net-(IC1-X1)") (class "Default")
      (node (ref "C21") (pin "1") (pinfunction "1_1") (pintype "passive"))
      (node (ref "IC1") (pin "45") (pinfunction "X1_45") (pintype "bidirectional"))
      (node (ref "R3") (pin "2") (pinfunction "2_2") (pintype "passive"))
      (node (ref "X4") (pin "2") (pinfunction "2_2") (pintype "bidirectional"))
    )
    (net (code "90") (name "Net-(IC1-X2)") (class "Default")
      (node (ref "C1") (pin "1") (pinfunction "1_1") (pintype "passive"))
      (node (ref "IC1") (pin "44") (pinfunction "X2_44") (pintype "bidirectional"))
      (node (ref "R3") (pin "1") (pinfunction "1_1") (pintype "passive"))
      (node (ref "X4") (pin "4") (pinfunction "4_4") (pintype "bidirectional"))
    )
    (net (code "91") (name "Net-(IC2-UCAP)") (class "Default")
      (node (ref "C30") (pin "1") (pinfunction "1_1") (pintype "passive"))
      (node (ref "IC2") (pin "6") (pinfunction "UCAP_6") (pintype "bidirectional"))
    )
    (net (code "92") (name "Net-(K1-Pad1)") (class "Default")
      (node (ref "K1") (pin "1") (pinfunction "1_1") (pintype "bidirectional"))
      (node (ref "R31") (pin "2") (pinfunction "2_2") (pintype "passive"))
    )
    (net (code "93") (name "Net-(Q1-G)") (class "Default")
      (node (ref "Q1") (pin "1") (pinfunction "G_1") (pintype "passive"))
      (node (ref "Q2") (pin "3") (pinfunction "C_3") (pintype "passive"))
      (node (ref "R36") (pin "1") (pinfunction "1_1") (pintype "passive"))
    )
    (net (code "94") (name "Net-(U1-~{HOLD}{slash}IO3)") (class "Default")
      (node (ref "R11") (pin "1") (pinfunction "1_1") (pintype "passive"))
      (node (ref "U1") (pin "7") (pinfunction "~{HOLD}/IO3_7") (pintype "bidirectional"))
    )
    (net (code "95") (name "Net-(U1-~{WP}{slash}IO2)") (class "Default")
      (node (ref "R10") (pin "2") (pinfunction "2_2") (pintype "passive"))
      (node (ref "U1") (pin "3") (pinfunction "~{WP}/IO2_3") (pintype "bidirectional"))
    )
    (net (code "96") (name "Net-(U2-VBUS_DET)") (class "Default")
      (node (ref "R20") (pin "1") (pinfunction "1_1") (pintype "passive"))
      (node (ref "U2") (pin "5") (pinfunction "VBUS_DET_5") (pintype "input"))
    )
    (net (code "97") (name "Net-(U3-LED)") (class "Default")
      (node (ref "R23") (pin "1") (pinfunction "1_1") (pintype "passive"))
      (node (ref "U3") (pin "21") (pinfunction "LED_21") (pintype "bidirectional"))
    )
    (net (code "98") (name "Net-(U3-RTERM)") (class "Default")
      (node (ref "R22") (pin "2") (pinfunction "2_2") (pintype "passive"))
      (node (ref "U3") (pin "16") (pinfunction "RTERM_16") (pintype "bidirectional"))
    )
    (net (code "99") (name "Net-(U3-SD1_CDZ)") (class "Default")
      (node (ref "R21") (pin "2") (pinfunction "2_2") (pintype "passive"))
      (node (ref "U3") (pin "1") (pinfunction "SD1_CDZ_1") (pintype "bidirectional"))
    )
    (net (code "100") (name "Net-(U4-FB)") (class "Default")
      (node (ref "C11") (pin "1") (pinfunction "1_1") (pintype "passive"))
      (node (ref "R6") (pin "2") (pinfunction "2_2") (pintype "passive"))
      (node (ref "R9") (pin "1") (pinfunction "1_1") (pintype "passive"))
      (node (ref "U4") (pin "5") (pinfunction "FB_5") (pintype "bidirectional"))
    )
    (net (code "101") (name "Net-(U4-LX)") (class "Default")
      (node (ref "L1") (pin "1") (pinfunction "1_1") (pintype "passive"))
      (node (ref "U4") (pin "3") (pinfunction "LX_3") (pintype "bidirectional"))
    )
    (net (code "102") (name "Net-(U5-FB)") (class "Default")
      (node (ref "C58") (pin "1") (pinfunction "1_1") (pintype "passive"))
      (node (ref "R12") (pin "2") (pinfunction "2_2") (pintype "passive"))
      (node (ref "R13") (pin "1") (pinfunction "1_1") (pintype "passive"))
      (node (ref "U5") (pin "5") (pinfunction "FB_5") (pintype "bidirectional"))
    )
    (net (code "103") (name "Net-(U5-LX)") (class "Default")
      (node (ref "L10") (pin "1") (pinfunction "1_1") (pintype "passive"))
      (node (ref "U5") (pin "3") (pinfunction "LX_3") (pintype "bidirectional"))
    )
    (net (code "104") (name "Net-(U6-OUT)") (class "Default")
      (node (ref "C26") (pin "2") (pinfunction "2_2") (pintype "passive"))
      (node (ref "C27") (pin "2") (pinfunction "2_2") (pintype "passive"))
      (node (ref "C28") (pin "2") (pinfunction "2_2") (pintype "passive"))
      (node (ref "L2") (pin "1") (pinfunction "1_1") (pintype "passive"))
      (node (ref "U6") (pin "1") (pinfunction "OUT_1") (pintype "bidirectional"))
    )
    (net (code "105") (name "Net-(U7-OUT)") (class "Default")
      (node (ref "C32") (pin "2") (pinfunction "2_2") (pintype "passive"))
      (node (ref "C38") (pin "2") (pinfunction "2_2") (pintype "passive"))
      (node (ref "C39") (pin "2") (pinfunction "2_2") (pintype "passive"))
      (node (ref "L4") (pin "1") (pinfunction "1_1") (pintype "passive"))
      (node (ref "U7") (pin "1") (pinfunction "OUT_1") (pintype "bidirectional"))
    )
    (net (code "106") (name "Net-(U8-OUT)") (class "Default")
      (node (ref "C53") (pin "2") (pinfunction "2_2") (pintype "passive"))
      (node (ref "C54") (pin "2") (pinfunction "2_2") (pintype "passive"))
      (node (ref "C55") (pin "2") (pinfunction "2_2") (pintype "passive"))
      (node (ref "L9") (pin "1") (pinfunction "1_1") (pintype "passive"))
      (node (ref "U8") (pin "1") (pinfunction "OUT_1") (pintype "bidirectional"))
    )
    (net (code "107") (name "OUT1") (class "Default")
      (node (ref "R18") (pin "1") (pinfunction "1_1") (pintype "passive"))
      (node (ref "U2") (pin "25") (pinfunction "SDA_OUT1_25") (pintype "bidirectional"))
    )
    (net (code "108") (name "OUT2") (class "Default")
      (node (ref "R19") (pin "1") (pinfunction "1_1") (pintype "passive"))
      (node (ref "U2") (pin "26") (pinfunction "SCL_OUT2_26") (pintype "bidirectional"))
    )
    (net (code "109") (name "PLED{slash}FN_C") (class "Default")
      (node (ref "IC1") (pin "32") (pinfunction "PLED/FN_C_32") (pintype "bidirectional"))
      (node (ref "R45") (pin "2") (pinfunction "2_2") (pintype "passive"))
    )
    (net (code "110") (name "RESET") (class "Default")
      (node (ref "C95") (pin "1") (pinfunction "1_1") (pintype "passive"))
      (node (ref "IC2") (pin "13") (pinfunction "~{RESET}_13") (pintype "bidirectional"))
      (node (ref "J10") (pin "3") (pinfunction "3_3") (pintype "bidirectional"))
      (node (ref "R30") (pin "1") (pinfunction "1_1") (pintype "passive"))
      (node (ref "R31") (pin "1") (pinfunction "1_1") (pintype "passive"))
    )
    (net (code "111") (name "RESETJ") (class "Default")
      (node (ref "C25") (pin "1") (pinfunction "1_1") (pintype "passive"))
      (node (ref "IC1") (pin "24") (pinfunction "RESETJ_24") (pintype "bidirectional"))
      (node (ref "R1") (pin "2") (pinfunction "2_2") (pintype "passive"))
      (node (ref "R2") (pin "1") (pinfunction "1_1") (pintype "passive"))
    )
    (net (code "112") (name "RTERM") (class "Default")
      (node (ref "IC1") (pin "16") (pinfunction "RTERM_16") (pintype "bidirectional"))
      (node (ref "R4") (pin "2") (pinfunction "2_2") (pintype "passive"))
    )
    (net (code "113") (name "RX_UP_N") (class "Default")
      (node (ref "IC1") (pin "41") (pinfunction "RXN1_P0_41") (pintype "bidirectional"))
      (node (ref "U2") (pin "10") (pinfunction "RXN_10") (pintype "bidirectional"))
    )
    (net (code "114") (name "RX_UP_P") (class "Default")
      (node (ref "IC1") (pin "42") (pinfunction "RXP1_P0_42") (pintype "bidirectional"))
      (node (ref "U2") (pin "9") (pinfunction "RXP_9") (pintype "bidirectional"))
    )
    (net (code "115") (name "SCK") (class "Default")
      (node (ref "IC2") (pin "9") (pinfunction "(PCINT1/SCLK)_PB1_9") (pintype "bidirectional"))
      (node (ref "J10") (pin "2") (pinfunction "2_2") (pintype "bidirectional"))
    )
    (net (code "116") (name "SCL") (class "Default")
      (node (ref "IC2") (pin "18") (pinfunction "(OC0B/SCL/INT0)_PD0_18") (pintype "bidirectional"))
      (node (ref "J6") (pin "4") (pinfunction "S_4") (pintype "passive"))
      (node (ref "R15") (pin "2") (pinfunction "2_2") (pintype "passive"))
    )
    (net (code "117") (name "SDA") (class "Default")
      (node (ref "IC2") (pin "19") (pinfunction "(SDA/INT1)_PD1_19") (pintype "bidirectional"))
      (node (ref "J6") (pin "3") (pinfunction "S_3") (pintype "passive"))
      (node (ref "R27") (pin "2") (pinfunction "2_2") (pintype "passive"))
    )
    (net (code "118") (name "SPI_CK") (class "Default")
      (node (ref "IC1") (pin "29") (pinfunction "P_SPI_CK_29") (pintype "bidirectional"))
      (node (ref "U1") (pin "6") (pinfunction "CLK_6") (pintype "bidirectional"))
    )
    (net (code "119") (name "SPI_CZ") (class "Default")
      (node (ref "IC1") (pin "31") (pinfunction "P_SPI_CZ_31") (pintype "bidirectional"))
      (node (ref "U1") (pin "1") (pinfunction "~{CS}_1") (pintype "bidirectional"))
    )
    (net (code "120") (name "SPI_DI") (class "Default")
      (node (ref "IC1") (pin "30") (pinfunction "P_SPI_DI_30") (pintype "bidirectional"))
      (node (ref "U1") (pin "2") (pinfunction "DO/IO1_2") (pintype "bidirectional"))
    )
    (net (code "121") (name "SPI_DO") (class "Default")
      (node (ref "IC1") (pin "28") (pinfunction "P_SPI_DO_28") (pintype "bidirectional"))
      (node (ref "U1") (pin "5") (pinfunction "DI/IO0_5") (pintype "bidirectional"))
    )
    (net (code "122") (name "TEMP") (class "Default")
      (node (ref "IC2") (pin "41") (pinfunction "PF0_(ADC0)_41") (pintype "bidirectional"))
      (node (ref "R51") (pin "2") (pinfunction "2_2") (pintype "passive"))
      (node (ref "RT1") (pin "1") (pinfunction "1_1") (pintype "bidirectional"))
    )
    (net (code "123") (name "TX1_N") (class "Default")
      (node (ref "C5") (pin "2") (pinfunction "2_2") (pintype "passive"))
      (node (ref "U2") (pin "17") (pinfunction "TX1P_17") (pintype "bidirectional"))
    )
    (net (code "124") (name "TX1_P") (class "Default")
      (node (ref "C6") (pin "2") (pinfunction "2_2") (pintype "passive"))
      (node (ref "U2") (pin "16") (pinfunction "TX1N_16") (pintype "bidirectional"))
    )
    (net (code "125") (name "TX2_N") (class "Default")
      (node (ref "C7") (pin "2") (pinfunction "2_2") (pintype "passive"))
      (node (ref "U2") (pin "20") (pinfunction "TX2N_20") (pintype "bidirectional"))
    )
    (net (code "126") (name "TX2_P") (class "Default")
      (node (ref "C8") (pin "2") (pinfunction "2_2") (pintype "passive"))
      (node (ref "U2") (pin "21") (pinfunction "TX2P_21") (pintype "bidirectional"))
    )
    (net (code "127") (name "TXUP_N") (class "Default")
      (node (ref "C69") (pin "2") (pinfunction "2_2") (pintype "passive"))
      (node (ref "IC1") (pin "38") (pinfunction "TXN1_P0_38") (pintype "bidirectional"))
    )
    (net (code "128") (name "TXUP_P") (class "Default")
      (node (ref "C70") (pin "2") (pinfunction "2_2") (pintype "passive"))
      (node (ref "IC1") (pin "39") (pinfunction "TXP1_P0_39") (pintype "bidirectional"))
    )
    (net (code "129") (name "TX_N") (class "Default")
      (node (ref "C69") (pin "1") (pinfunction "1_1") (pintype "passive"))
      (node (ref "U2") (pin "7") (pinfunction "TXN_7") (pintype "bidirectional"))
    )
    (net (code "130") (name "TX_P") (class "Default")
      (node (ref "C70") (pin "1") (pinfunction "1_1") (pintype "passive"))
      (node (ref "U2") (pin "6") (pinfunction "TXP_6") (pintype "bidirectional"))
    )
    (net (code "131") (name "UART_RX") (class "Default")
      (node (ref "IC2") (pin "20") (pinfunction "(RXD1/INT2)_PD2_20") (pintype "bidirectional"))
      (node (ref "Q4") (pin "3") (pinfunction "D_3") (pintype "passive"))
      (node (ref "R48") (pin "2") (pinfunction "2_2") (pintype "passive"))
    )
    (net (code "132") (name "UART_TX") (class "Default")
      (node (ref "IC2") (pin "21") (pinfunction "(TXD1/INT3)_PD3_21") (pintype "bidirectional"))
      (node (ref "Q3") (pin "3") (pinfunction "D_3") (pintype "passive"))
      (node (ref "R47") (pin "2") (pinfunction "2_2") (pintype "passive"))
    )
    (net (code "133") (name "USB3TXE_N") (class "Default")
      (node (ref "C16") (pin "2") (pinfunction "2_2") (pintype "passive"))
      (node (ref "J3") (pin "7") (pinfunction "7_7") (pintype "bidirectional"))
    )
    (net (code "134") (name "USB3TXE_P") (class "Default")
      (node (ref "C15") (pin "2") (pinfunction "2_2") (pintype "passive"))
      (node (ref "J3") (pin "8") (pinfunction "8_8") (pintype "bidirectional"))
    )
    (net (code "135") (name "VBUS") (class "Default")
      (node (ref "C10") (pin "2") (pinfunction "2_2") (pintype "passive"))
      (node (ref "C101") (pin "1") (pinfunction "1_1") (pintype "passive"))
      (node (ref "C18") (pin "2") (pinfunction "2_2") (pintype "passive"))
      (node (ref "C20") (pin "2") (pinfunction "2_2") (pintype "passive"))
      (node (ref "C23") (pin "2") (pinfunction "2_2") (pintype "passive"))
      (node (ref "C29") (pin "1") (pinfunction "1_1") (pintype "passive"))
      (node (ref "C45") (pin "2") (pinfunction "2_2") (pintype "passive"))
      (node (ref "C46") (pin "2") (pinfunction "2_2") (pintype "passive"))
      (node (ref "C47") (pin "2") (pinfunction "2_2") (pintype "passive"))
      (node (ref "C56") (pin "2") (pinfunction "2_2") (pintype "passive"))
      (node (ref "C57") (pin "2") (pinfunction "2_2") (pintype "passive"))
      (node (ref "C86") (pin "2") (pinfunction "2_2") (pintype "passive"))
      (node (ref "C9") (pin "2") (pinfunction "2_2") (pintype "passive"))
      (node (ref "C96") (pin "2") (pinfunction "2_2") (pintype "passive"))
      (node (ref "C97") (pin "2") (pinfunction "2_2") (pintype "passive"))
      (node (ref "L3") (pin "1") (pinfunction "1_1") (pintype "passive"))
      (node (ref "L7") (pin "1") (pinfunction "1_1") (pintype "passive"))
      (node (ref "L8") (pin "1") (pinfunction "1_1") (pintype "passive"))
      (node (ref "Q1") (pin "2") (pinfunction "S_2") (pintype "passive"))
      (node (ref "R1") (pin "1") (pinfunction "1_1") (pintype "passive"))
      (node (ref "R18") (pin "2") (pinfunction "2_2") (pintype "passive"))
      (node (ref "R19") (pin "2") (pinfunction "2_2") (pintype "passive"))
      (node (ref "R20") (pin "2") (pinfunction "2_2") (pintype "passive"))
      (node (ref "R34") (pin "2") (pinfunction "2_2") (pintype "passive"))
      (node (ref "R36") (pin "2") (pinfunction "2_2") (pintype "passive"))
      (node (ref "R5") (pin "2") (pinfunction "2_2") (pintype "passive"))
      (node (ref "U2") (pin "30") (pinfunction "VDD5_30") (pintype "power_in"))
      (node (ref "U4") (pin "1") (pinfunction "EN_1") (pintype "bidirectional"))
      (node (ref "U4") (pin "4") (pinfunction "IN_4") (pintype "bidirectional"))
      (node (ref "U5") (pin "1") (pinfunction "EN_1") (pintype "bidirectional"))
      (node (ref "U5") (pin "4") (pinfunction "IN_4") (pintype "bidirectional"))
      (node (ref "U6") (pin "5") (pinfunction "IN_5") (pintype "bidirectional"))
      (node (ref "U7") (pin "5") (pinfunction "IN_5") (pintype "bidirectional"))
      (node (ref "U8") (pin "5") (pinfunction "IN_5") (pintype "bidirectional"))
    )
    (net (code "136") (name "VBUS1") (class "Default")
      (node (ref "C19") (pin "1") (pinfunction "1_1") (pintype "passive"))
      (node (ref "J9") (pin "1") (pinfunction "1_1") (pintype "bidirectional"))
      (node (ref "J9") (pin "2") (pinfunction "2_2") (pintype "bidirectional"))
      (node (ref "L4") (pin "2") (pinfunction "2_2") (pintype "passive"))
    )
    (net (code "137") (name "VBUS2") (class "Default")
      (node (ref "C24") (pin "1") (pinfunction "1_1") (pintype "passive"))
      (node (ref "J3") (pin "1") (pinfunction "1_1") (pintype "bidirectional"))
      (node (ref "J3") (pin "2") (pinfunction "2_2") (pintype "bidirectional"))
      (node (ref "L2") (pin "2") (pinfunction "2_2") (pintype "passive"))
    )
    (net (code "138") (name "VBUS3") (class "Default")
      (node (ref "C40") (pin "2") (pinfunction "2_2") (pintype "passive"))
      (node (ref "C52") (pin "1") (pinfunction "1_1") (pintype "passive"))
      (node (ref "L9") (pin "2") (pinfunction "2_2") (pintype "passive"))
      (node (ref "U3") (pin "22") (pinfunction "VBUS_22") (pintype "bidirectional"))
    )
    (net (code "139") (name "VBUS4") (class "Default")
      (node (ref "C22") (pin "1") (pinfunction "1_1") (pintype "passive"))
      (node (ref "J1") (pin "5") (pinfunction "5_5") (pintype "bidirectional"))
      (node (ref "J1") (pin "6") (pinfunction "6_6") (pintype "bidirectional"))
      (node (ref "L7") (pin "2") (pinfunction "2_2") (pintype "passive"))
    )
    (net (code "140") (name "VBUS5") (class "Default")
      (node (ref "C44") (pin "1") (pinfunction "1_1") (pintype "passive"))
      (node (ref "J4") (pin "2") (pinfunction "2_2") (pintype "bidirectional"))
      (node (ref "L8") (pin "2") (pinfunction "2_2") (pintype "passive"))
    )
    (net (code "141") (name "VBUS6") (class "Default")
      (node (ref "C17") (pin "1") (pinfunction "1_1") (pintype "passive"))
      (node (ref "C89") (pin "1") (pinfunction "1_1") (pintype "passive"))
      (node (ref "C90") (pin "1") (pinfunction "1_1") (pintype "passive"))
      (node (ref "IC2") (pin "2") (pinfunction "UVCC_2") (pintype "bidirectional"))
      (node (ref "IC2") (pin "7") (pinfunction "VBUS_7") (pintype "bidirectional"))
      (node (ref "L3") (pin "2") (pinfunction "2_2") (pintype "passive"))
    )
    (net (code "142") (name "VBUS_IN") (class "Default")
      (node (ref "IC1") (pin "25") (pinfunction "VBUS_25") (pintype "bidirectional"))
      (node (ref "R34") (pin "1") (pinfunction "1_1") (pintype "passive"))
      (node (ref "R39") (pin "2") (pinfunction "2_2") (pintype "passive"))
    )
    (net (code "143") (name "VCCQ") (class "Default")
      (node (ref "C74") (pin "2") (pinfunction "2_2") (pintype "passive"))
      (node (ref "C81") (pin "2") (pinfunction "2_2") (pintype "passive"))
      (node (ref "C82") (pin "2") (pinfunction "2_2") (pintype "passive"))
      (node (ref "H1") (pin "C6") (pinfunction "VCCQ_1_C6") (pintype "bidirectional"))
      (node (ref "H1") (pin "M4") (pinfunction "VCCQ_2_M4") (pintype "bidirectional"))
      (node (ref "H1") (pin "P3") (pinfunction "VCCQ_3_P3") (pintype "bidirectional"))
      (node (ref "H1") (pin "P5") (pinfunction "VCCQ_4_P5") (pintype "bidirectional"))
      (node (ref "R25") (pin "1") (pinfunction "1_1") (pintype "passive"))
      (node (ref "U3") (pin "33") (pinfunction "VUHS_2_33") (pintype "bidirectional"))
      (node (ref "U3") (pin "43") (pinfunction "VUHS_1_43") (pintype "bidirectional"))
    )
    (net (code "144") (name "VSSP") (class "Default")
      (node (ref "IC1") (pin "18") (pinfunction "VSSP_18") (pintype "bidirectional"))
      (node (ref "R42") (pin "2") (pinfunction "2_2") (pintype "passive"))
    )
    (net (code "145") (name "X1") (class "Default")
      (node (ref "C77") (pin "1") (pinfunction "1_1") (pintype "passive"))
      (node (ref "R26") (pin "2") (pinfunction "2_2") (pintype "passive"))
      (node (ref "U3") (pin "13") (pinfunction "X1_13") (pintype "bidirectional"))
      (node (ref "X3") (pin "2") (pinfunction "2_2") (pintype "bidirectional"))
    )
    (net (code "146") (name "X2") (class "Default")
      (node (ref "C76") (pin "1") (pinfunction "1_1") (pintype "passive"))
      (node (ref "R26") (pin "1") (pinfunction "1_1") (pintype "passive"))
      (node (ref "U3") (pin "14") (pinfunction "X2_14") (pintype "bidirectional"))
      (node (ref "X3") (pin "4") (pinfunction "4_4") (pintype "bidirectional"))
    )
    (net (code "147") (name "XTAL1") (class "Default")
      (node (ref "C31") (pin "1") (pinfunction "1_1") (pintype "passive"))
      (node (ref "IC2") (pin "17") (pinfunction "XTAL1_17") (pintype "bidirectional"))
      (node (ref "X1") (pin "2") (pinfunction "2_2") (pintype "bidirectional"))
    )
    (net (code "148") (name "XTAL2") (class "Default")
      (node (ref "C85") (pin "1") (pinfunction "1_1") (pintype "passive"))
      (node (ref "IC2") (pin "16") (pinfunction "XTAL2_16") (pintype "bidirectional"))
      (node (ref "X1") (pin "4") (pinfunction "4_4") (pintype "bidirectional"))
    )
    (net (code "149") (name "unconnected-(H1-DS-PadH5)") (class "Default")
      (node (ref "H1") (pin "H5") (pinfunction "DS_H5") (pintype "bidirectional"))
    )
    (net (code "150") (name "unconnected-(IC1-OVCURJ-Pad33)") (class "Default")
      (node (ref "IC1") (pin "33") (pinfunction "OVCURJ_33") (pintype "bidirectional"))
    )
    (net (code "151") (name "unconnected-(IC1-PWRENJ-Pad34)") (class "Default")
      (node (ref "IC1") (pin "34") (pinfunction "PWRENJ_34") (pintype "bidirectional"))
    )
    (net (code "152") (name "unconnected-(IC1-RXN1_P1-Pad50)") (class "Default")
      (node (ref "IC1") (pin "50") (pinfunction "RXN1_P1_50") (pintype "bidirectional"))
    )
    (net (code "153") (name "unconnected-(IC1-RXP1_P1-Pad51)") (class "Default")
      (node (ref "IC1") (pin "51") (pinfunction "RXP1_P1_51") (pintype "bidirectional"))
    )
    (net (code "154") (name "unconnected-(IC1-SW-Pad19)") (class "Default")
      (node (ref "IC1") (pin "19") (pinfunction "SW_19") (pintype "bidirectional"))
    )
    (net (code "155") (name "unconnected-(IC1-TXN1_P1-Pad47)") (class "Default")
      (node (ref "IC1") (pin "47") (pinfunction "TXN1_P1_47") (pintype "bidirectional"))
    )
    (net (code "156") (name "unconnected-(IC1-TXP1_P1-Pad48)") (class "Default")
      (node (ref "IC1") (pin "48") (pinfunction "TXP1_P1_48") (pintype "bidirectional"))
    )
    (net (code "157") (name "unconnected-(IC2-(SS{slash}PCINT0)_PB0-Pad8)") (class "Default")
      (node (ref "IC2") (pin "8") (pinfunction "(SS/PCINT0)_PB0_8") (pintype "bidirectional"))
    )
    (net (code "158") (name "unconnected-(IC2-(XCK1{slash}~{CTS})_PD5-Pad22)") (class "Default")
      (node (ref "IC2") (pin "22") (pinfunction "(XCK1/~{CTS})_PD5_22") (pintype "bidirectional"))
    )
    (net (code "159") (name "unconnected-(IC2-PB5_(PCINT5{slash}OC1A{slash}~{OC4B}{slash}ADC12)-Pad29)") (class "Default")
      (node (ref "IC2") (pin "29") (pinfunction "PB5_(PCINT5/OC1A/~{OC4B}/ADC12)_29") (pintype "bidirectional"))
    )
    (net (code "160") (name "unconnected-(IC2-PE2_(H~{WB})-Pad33)") (class "Default")
      (node (ref "IC2") (pin "33") (pinfunction "PE2_(H~{WB})_33") (pintype "bidirectional"))
    )
    (net (code "161") (name "unconnected-(IC2-PF1_(ADC1)-Pad40)") (class "Default")
      (node (ref "IC2") (pin "40") (pinfunction "PF1_(ADC1)_40") (pintype "bidirectional"))
    )
    (net (code "162") (name "unconnected-(IC2-PF4_(ADC4{slash}TCK)-Pad39)") (class "Default")
      (node (ref "IC2") (pin "39") (pinfunction "PF4_(ADC4/TCK)_39") (pintype "bidirectional"))
    )
    (net (code "163") (name "unconnected-(IC2-PF5_(ADC5{slash}TMS)-Pad38)") (class "Default")
      (node (ref "IC2") (pin "38") (pinfunction "PF5_(ADC5/TMS)_38") (pintype "bidirectional"))
    )
    (net (code "164") (name "unconnected-(IC2-PF6_(ADC6{slash}TDO)-Pad37)") (class "Default")
      (node (ref "IC2") (pin "37") (pinfunction "PF6_(ADC6/TDO)_37") (pintype "bidirectional"))
    )
    (net (code "165") (name "unconnected-(J1-G1-PadMH1)") (class "Default")
      (node (ref "J1") (pin "MH1") (pinfunction "G1_MH1") (pintype "bidirectional"))
    )
    (net (code "166") (name "unconnected-(J1-G2-PadMH2)") (class "Default")
      (node (ref "J1") (pin "MH2") (pinfunction "G2_MH2") (pintype "bidirectional"))
    )
    (net (code "167") (name "unconnected-(J3-G1-PadP$13)") (class "Default")
      (node (ref "J3") (pin "P$13") (pinfunction "G1_P$13") (pintype "bidirectional"))
    )
    (net (code "168") (name "unconnected-(J3-G2-PadP$14)") (class "Default")
      (node (ref "J3") (pin "P$14") (pinfunction "G2_P$14") (pintype "bidirectional"))
    )
    (net (code "169") (name "unconnected-(J8-G1-PadP$13)") (class "Default")
      (node (ref "J8") (pin "P$13") (pinfunction "G1_P$13") (pintype "bidirectional"))
    )
    (net (code "170") (name "unconnected-(J8-G2-PadP$14)") (class "Default")
      (node (ref "J8") (pin "P$14") (pinfunction "G2_P$14") (pintype "bidirectional"))
    )
    (net (code "171") (name "unconnected-(J9-G1-PadP$13)") (class "Default")
      (node (ref "J9") (pin "P$13") (pinfunction "G1_P$13") (pintype "bidirectional"))
    )
    (net (code "172") (name "unconnected-(J9-G2-PadP$14)") (class "Default")
      (node (ref "J9") (pin "P$14") (pinfunction "G2_P$14") (pintype "bidirectional"))
    )
    (net (code "173") (name "unconnected-(U2-ADDR-Pad22)") (class "Default")
      (node (ref "U2") (pin "22") (pinfunction "ADDR_22") (pintype "input"))
    )
    (net (code "174") (name "unconnected-(U2-CURRENT_MODE-Pad3)") (class "Default")
      (node (ref "U2") (pin "3") (pinfunction "CURRENT_MODE_3") (pintype "input"))
    )
    (net (code "175") (name "unconnected-(U2-ID-Pad27)") (class "Default")
      (node (ref "U2") (pin "27") (pinfunction "ID_27") (pintype "open_collector"))
    )
    (net (code "176") (name "unconnected-(U2-INT_OUT3_N-Pad23)") (class "Default")
      (node (ref "U2") (pin "23") (pinfunction "INT_OUT3_N_23") (pintype "open_collector"))
    )
    (net (code "177") (name "unconnected-(U2-VCONN_FAULT_N-Pad24)") (class "Default")
      (node (ref "U2") (pin "24") (pinfunction "VCONN_FAULT_N_24") (pintype "open_collector"))
    )
    (net (code "178") (name "unconnected-(U3-DM-Pad4)") (class "Default")
      (node (ref "U3") (pin "4") (pinfunction "DM_4") (pintype "bidirectional"))
    )
    (net (code "179") (name "unconnected-(U3-DP-Pad5)") (class "Default")
      (node (ref "U3") (pin "5") (pinfunction "DP_5") (pintype "bidirectional"))
    )
    (net (code "180") (name "unconnected-(U3-MS1_INS{slash}SD1_WP-Pad2)") (class "Default")
      (node (ref "U3") (pin "2") (pinfunction "MS1_INS/SD1_WP_2") (pintype "bidirectional"))
    )
    (net (code "181") (name "unconnected-(U3-S1CK_M1D0-Pad39)") (class "Default")
      (node (ref "U3") (pin "39") (pinfunction "S1CK_M1D0_39") (pintype "bidirectional"))
    )
    (net (code "182") (name "unconnected-(U3-S1CM_M1D2-Pad40)") (class "Default")
      (node (ref "U3") (pin "40") (pinfunction "S1CM_M1D2_40") (pintype "bidirectional"))
    )
    (net (code "183") (name "unconnected-(U3-S1D4_M1D7-Pad48)") (class "Default")
      (node (ref "U3") (pin "48") (pinfunction "S1D4_M1D7_48") (pintype "bidirectional"))
    )
    (net (code "184") (name "unconnected-(U3-S1D5_M1D6-Pad47)") (class "Default")
      (node (ref "U3") (pin "47") (pinfunction "S1D5_M1D6_47") (pintype "bidirectional"))
    )
    (net (code "185") (name "unconnected-(U3-S1D6_M1D5-Pad46)") (class "Default")
      (node (ref "U3") (pin "46") (pinfunction "S1D6_M1D5_46") (pintype "bidirectional"))
    )
    (net (code "186") (name "unconnected-(U3-S1D7_M1D4-Pad45)") (class "Default")
      (node (ref "U3") (pin "45") (pinfunction "S1D7_M1D4_45") (pintype "bidirectional"))
    )
    (net (code "187") (name "unconnected-(U3-S2M2_VCC-Pad24)") (class "Default")
      (node (ref "U3") (pin "24") (pinfunction "S2M2_VCC_24") (pintype "bidirectional"))
    )
    (net (code "188") (name "unconnected-(U3-SPI_CLK-Pad19)") (class "Default")
      (node (ref "U3") (pin "19") (pinfunction "SPI_CLK_19") (pintype "bidirectional"))
    )
    (net (code "189") (name "unconnected-(U3-SPI_CS-Pad20)") (class "Default")
      (node (ref "U3") (pin "20") (pinfunction "SPI_CS_20") (pintype "bidirectional"))
    )
    (net (code "190") (name "unconnected-(U3-SPI_MISO-Pad17)") (class "Default")
      (node (ref "U3") (pin "17") (pinfunction "SPI_MISO_17") (pintype "bidirectional"))
    )
    (net (code "191") (name "unconnected-(U3-SPI_MOSI-Pad18)") (class "Default")
      (node (ref "U3") (pin "18") (pinfunction "SPI_MOSI_18") (pintype "bidirectional"))
    )
    (net (code "192") (name "unconnected-(USBC1-SBU1-PadA8)") (class "Default")
      (node (ref "USBC1") (pin "A8") (pinfunction "SBU1_A8") (pintype "passive"))
    )
    (net (code "193") (name "unconnected-(USBC1-SBU2-PadB8)") (class "Default")
      (node (ref "USBC1") (pin "B8") (pinfunction "SBU2_B8") (pintype "passive"))
    )
    (net (code "194") (name "~{FLT1}") (class "Default")
      (node (ref "IC2") (pin "27") (pinfunction "PD7_(T0/OC4D/ADC10)_27") (pintype "bidirectional"))
      (node (ref "R33") (pin "2") (pinfunction "2_2") (pintype "passive"))
      (node (ref "U6") (pin "3") (pinfunction "~{FLT}_3") (pintype "bidirectional"))
    )
    (net (code "195") (name "~{FLT2}") (class "Default")
      (node (ref "IC2") (pin "25") (pinfunction "PD4_(ICP1/ADC8)_25") (pintype "bidirectional"))
      (node (ref "R40") (pin "2") (pinfunction "2_2") (pintype "passive"))
      (node (ref "U7") (pin "3") (pinfunction "~{FLT}_3") (pintype "bidirectional"))
    )
    (net (code "196") (name "~{FLT3}") (class "Default")
      (node (ref "IC2") (pin "36") (pinfunction "PF7_(ADC7/TDI)_36") (pintype "bidirectional"))
      (node (ref "R17") (pin "2") (pinfunction "2_2") (pintype "passive"))
      (node (ref "U8") (pin "3") (pinfunction "~{FLT}_3") (pintype "bidirectional"))
    )
  )
)
